# unimodule.net
KiCad netlist of a schematic drawn in EAGLE
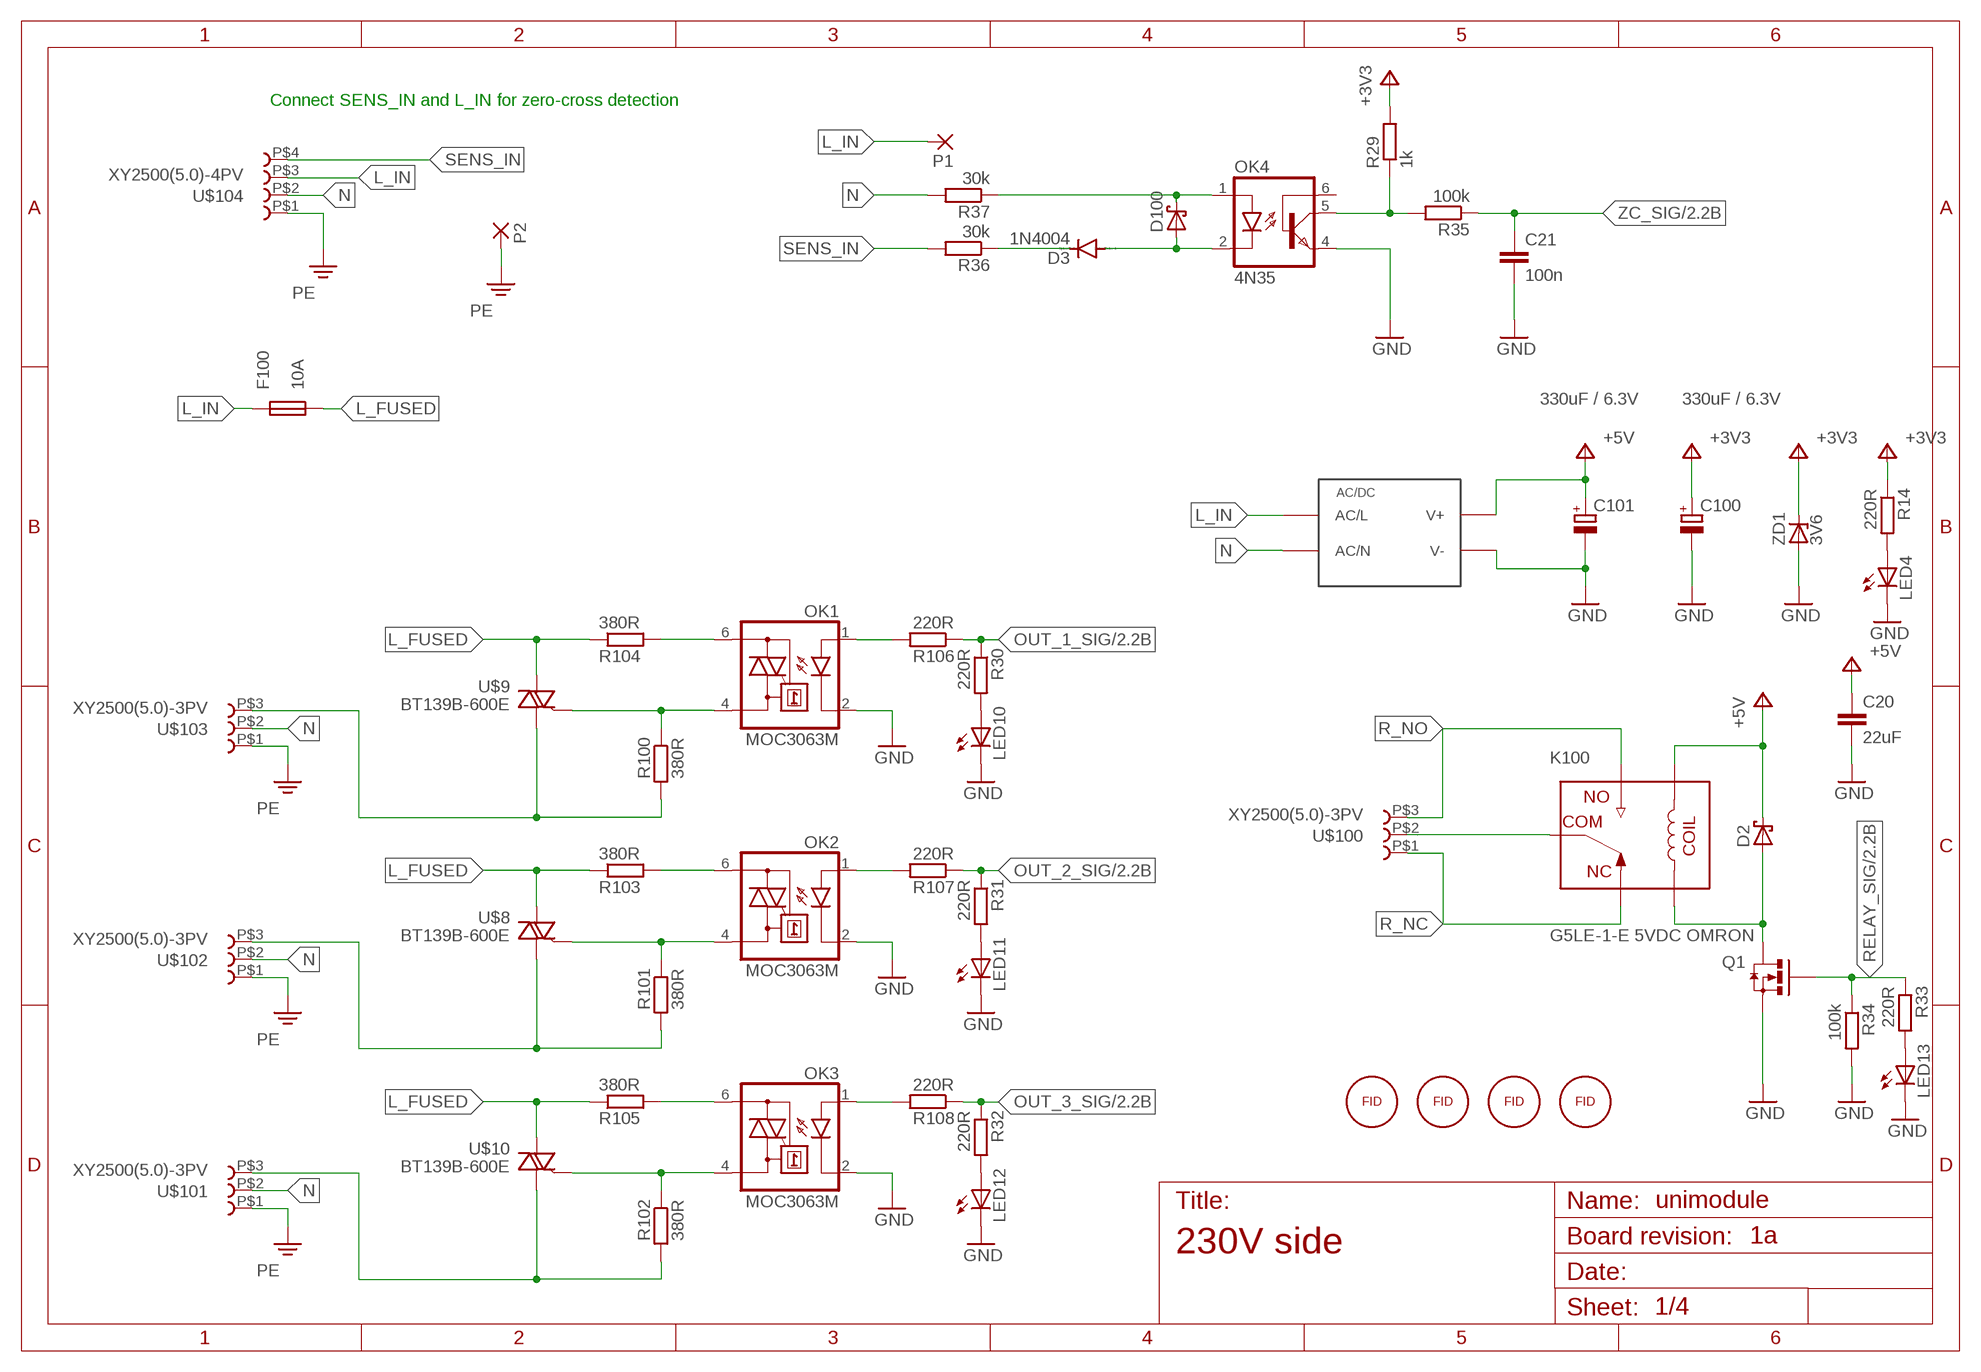
[diagram p0: schematic, sheet 1]
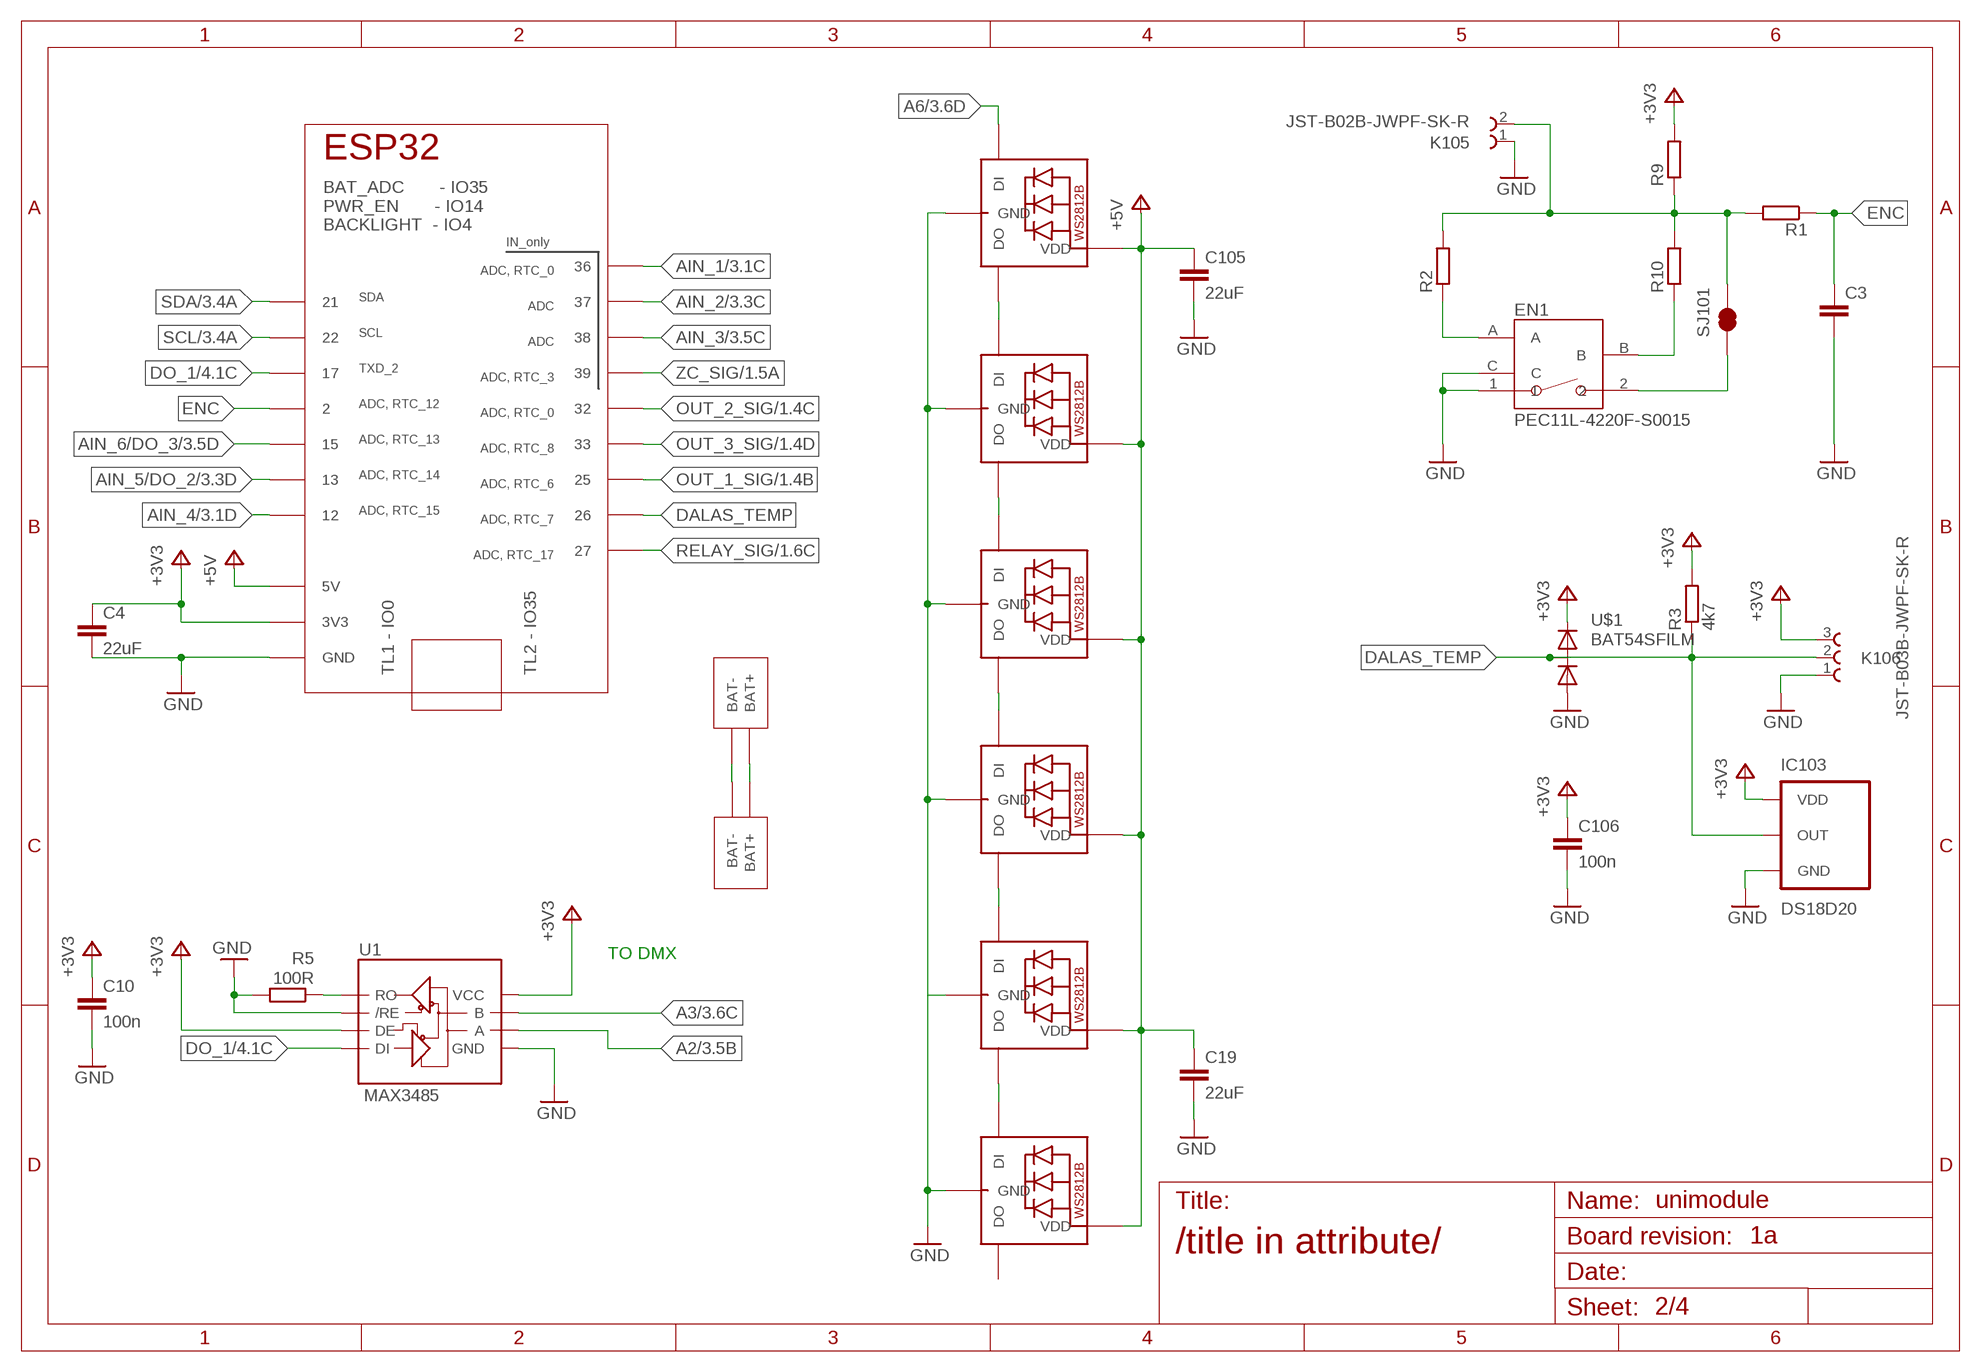
[diagram p1: schematic, sheet 2]
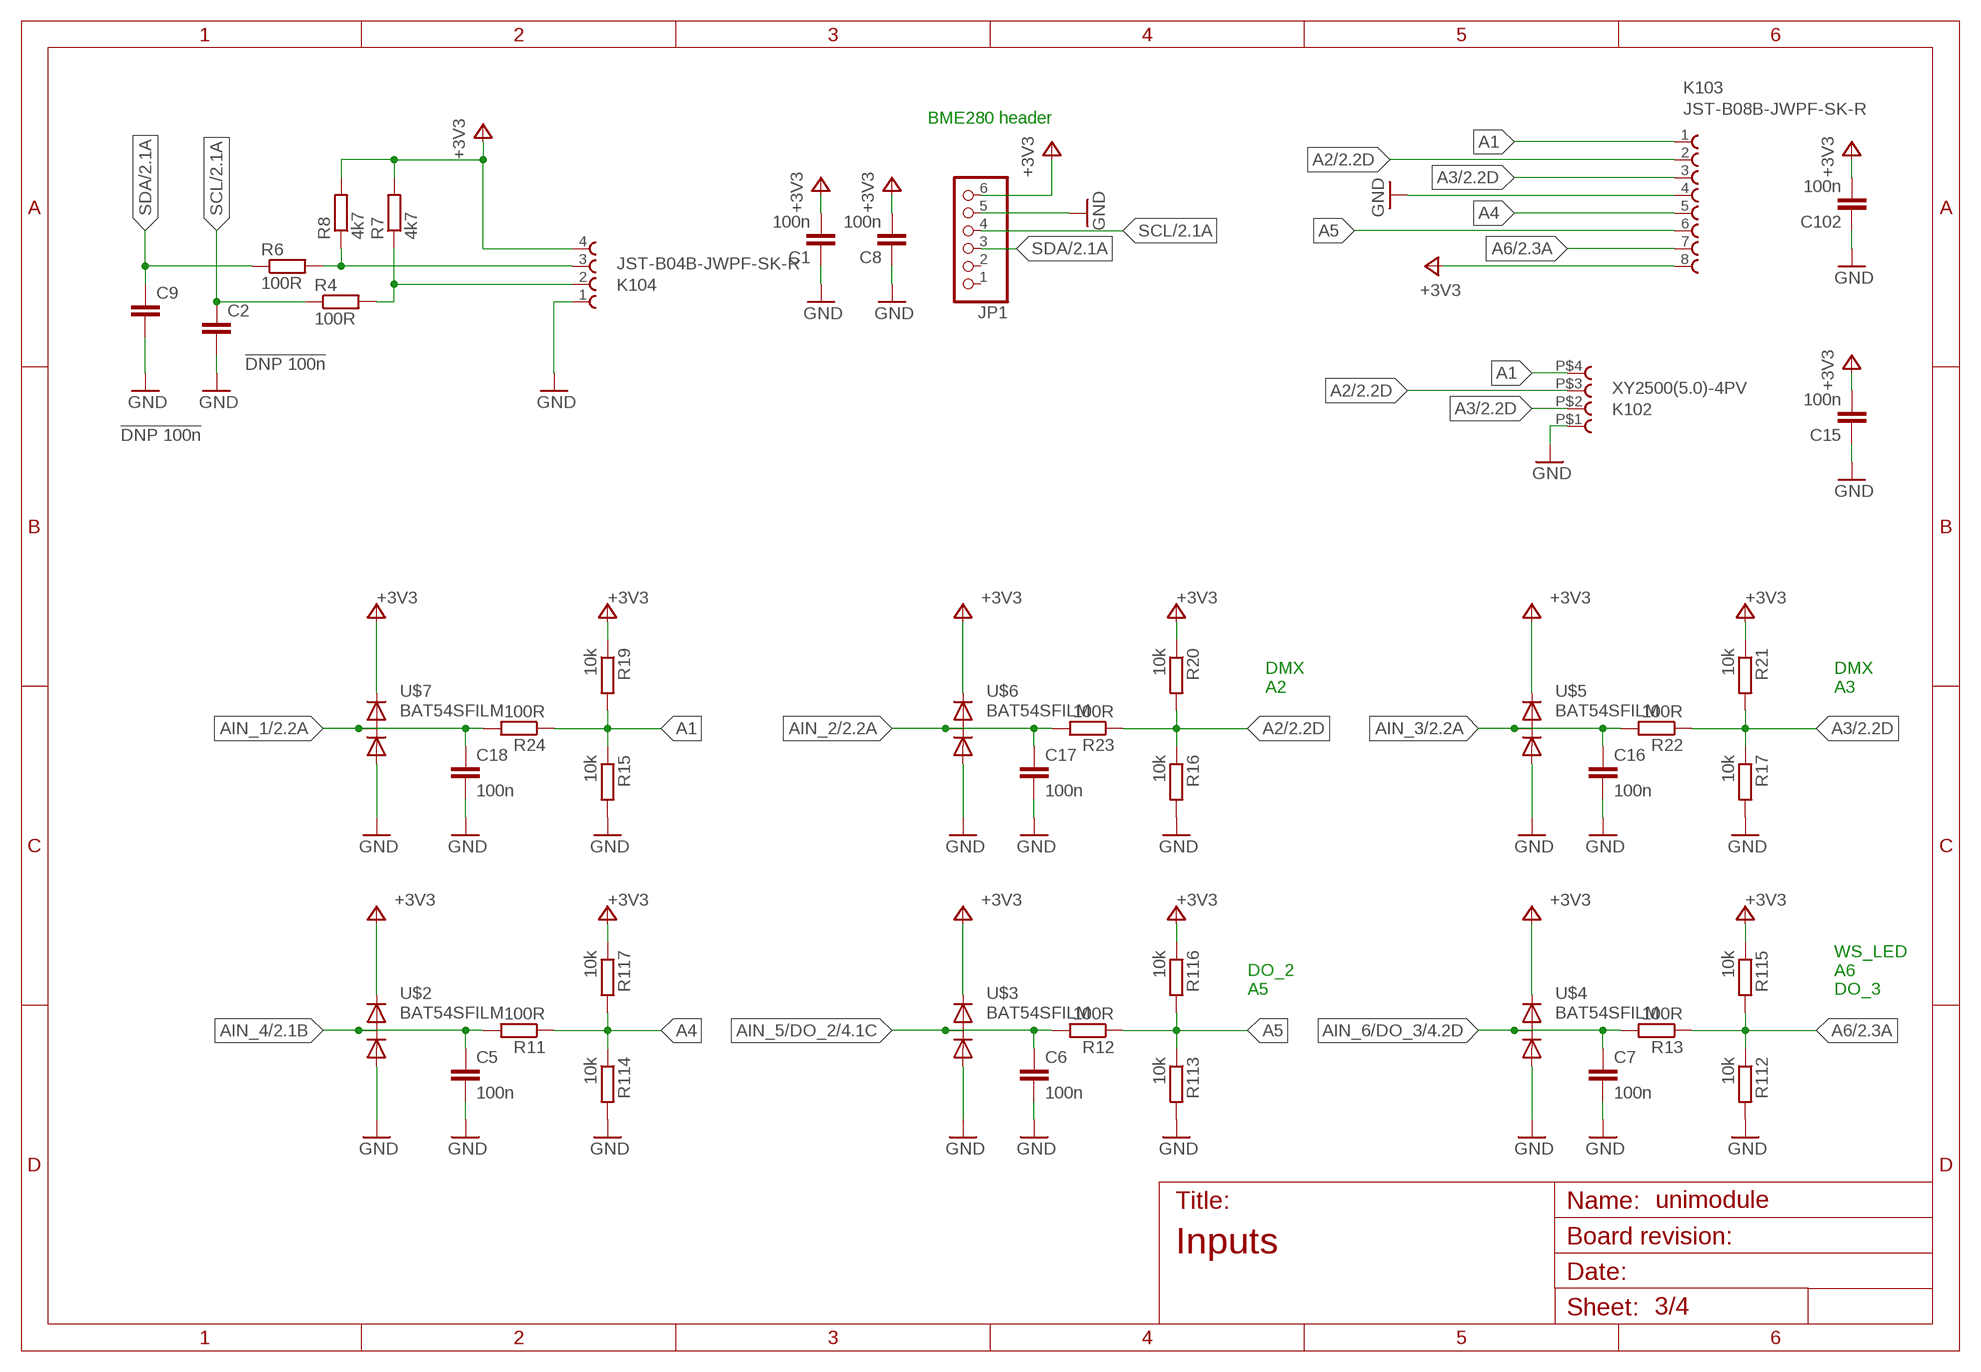
[diagram p2: schematic, sheet 3]
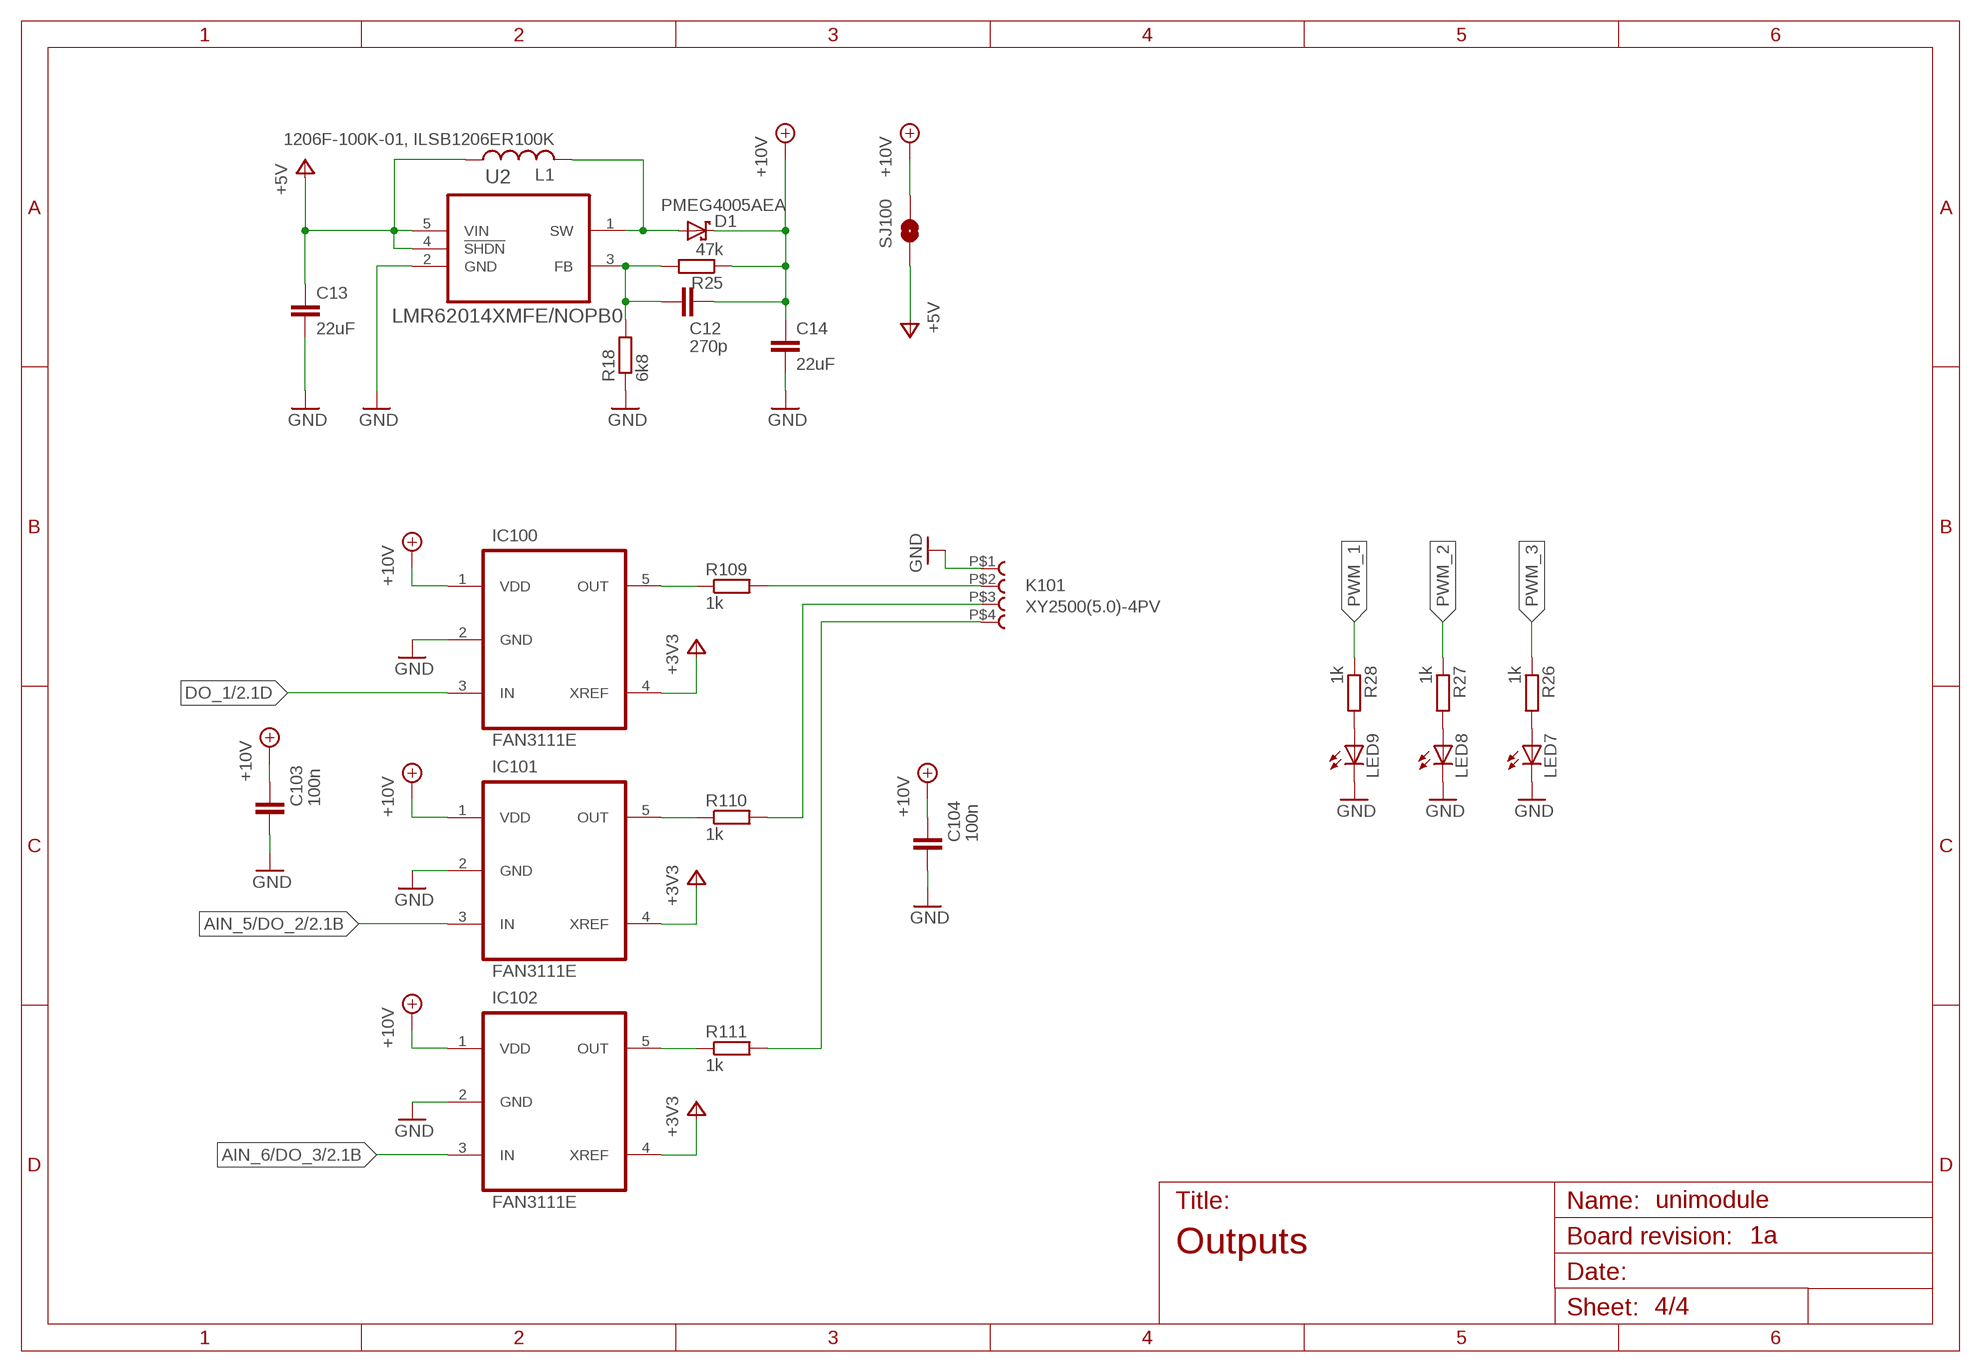
[diagram p3: schematic, sheet 4]

(export (version "E")
  (design (tool "Eeschema 10.0.6"))
  (components
    (comp (ref "C1")
      (value "100n")
      (footprint "eagle-import:C0603")
      (libsource (lib "eagle-import") (part "rcl_334_C-EUC0603"))
    )
    (comp (ref "C2")
      (value "!DNP 100n")
      (footprint "eagle-import:C0603")
      (libsource (lib "eagle-import") (part "rcl_334_C-EUC0603"))
    )
    (comp (ref "C5")
      (value "100n")
      (footprint "eagle-import:C0603")
      (libsource (lib "eagle-import") (part "rcl_334_C-EUC0603"))
    )
    (comp (ref "C6")
      (value "100n")
      (footprint "eagle-import:C0603")
      (libsource (lib "eagle-import") (part "rcl_334_C-EUC0603"))
    )
    (comp (ref "C7")
      (value "100n")
      (footprint "eagle-import:C0603")
      (libsource (lib "eagle-import") (part "rcl_334_C-EUC0603"))
    )
    (comp (ref "C8")
      (value "100n")
      (footprint "eagle-import:C0603")
      (libsource (lib "eagle-import") (part "rcl_334_C-EUC0603"))
    )
    (comp (ref "C9")
      (value "!DNP 100n")
      (footprint "eagle-import:C0603")
      (libsource (lib "eagle-import") (part "rcl_334_C-EUC0603"))
    )
    (comp (ref "C15")
      (value "100n")
      (footprint "eagle-import:C0603")
      (libsource (lib "eagle-import") (part "rcl_334_C-EUC0603"))
    )
    (comp (ref "C16")
      (value "100n")
      (footprint "eagle-import:C0603")
      (libsource (lib "eagle-import") (part "rcl_334_C-EUC0603"))
    )
    (comp (ref "C17")
      (value "100n")
      (footprint "eagle-import:C0603")
      (libsource (lib "eagle-import") (part "rcl_334_C-EUC0603"))
    )
    (comp (ref "C18")
      (value "100n")
      (footprint "eagle-import:C0603")
      (libsource (lib "eagle-import") (part "rcl_334_C-EUC0603"))
    )
    (comp (ref "C102")
      (value "100n")
      (footprint "eagle-import:C0603")
      (libsource (lib "eagle-import") (part "rcl_334_C-EUC0603"))
    )
    (comp (ref "JP1")
      (value "PINHD-1X6")
      (footprint "eagle-import:1X06")
      (libsource (lib "eagle-import") (part "PINHD-1X6"))
    )
    (comp (ref "K102")
      (value "XY2500(5.0)-4PV")
      (footprint "eagle-import:XY2500V-B_4P")
      (libsource (lib "eagle-import") (part "XY2500(5.0)-4PV"))
    )
    (comp (ref "K103")
      (value "JST-B08B-JWPF-SK-R")
      (footprint "eagle-import:JST-B08B-JWPF-SK-R")
      (libsource (lib "eagle-import") (part "JST-B08B-JWPF-SK-R"))
    )
    (comp (ref "K104")
      (value "JST-B04B-JWPF-SK-R")
      (footprint "eagle-import:JST-B04B-JWPF-SK-R")
      (libsource (lib "eagle-import") (part "JST-B04B-JWPF-SK-R"))
    )
    (comp (ref "R4")
      (value "100R")
      (footprint "eagle-import:R0603")
      (libsource (lib "eagle-import") (part "R-EU_R0603"))
    )
    (comp (ref "R6")
      (value "100R")
      (footprint "eagle-import:R0603")
      (libsource (lib "eagle-import") (part "R-EU_R0603"))
    )
    (comp (ref "R7")
      (value "4k7")
      (footprint "eagle-import:R0603")
      (libsource (lib "eagle-import") (part "R-EU_R0603"))
    )
    (comp (ref "R8")
      (value "4k7")
      (footprint "eagle-import:R0603")
      (libsource (lib "eagle-import") (part "R-EU_R0603"))
    )
    (comp (ref "R11")
      (value "100R")
      (footprint "eagle-import:R0603")
      (libsource (lib "eagle-import") (part "R-EU_R0603"))
    )
    (comp (ref "R12")
      (value "100R")
      (footprint "eagle-import:R0603")
      (libsource (lib "eagle-import") (part "R-EU_R0603"))
    )
    (comp (ref "R13")
      (value "100R")
      (footprint "eagle-import:R0603")
      (libsource (lib "eagle-import") (part "R-EU_R0603"))
    )
    (comp (ref "R15")
      (value "10k")
      (footprint "eagle-import:R0603")
      (libsource (lib "eagle-import") (part "R-EU_R0603"))
    )
    (comp (ref "R16")
      (value "10k")
      (footprint "eagle-import:R0603")
      (libsource (lib "eagle-import") (part "R-EU_R0603"))
    )
    (comp (ref "R17")
      (value "10k")
      (footprint "eagle-import:R0603")
      (libsource (lib "eagle-import") (part "R-EU_R0603"))
    )
    (comp (ref "R19")
      (value "10k")
      (footprint "eagle-import:R0603")
      (libsource (lib "eagle-import") (part "R-EU_R0603"))
    )
    (comp (ref "R20")
      (value "10k")
      (footprint "eagle-import:R0603")
      (libsource (lib "eagle-import") (part "R-EU_R0603"))
    )
    (comp (ref "R21")
      (value "10k")
      (footprint "eagle-import:R0603")
      (libsource (lib "eagle-import") (part "R-EU_R0603"))
    )
    (comp (ref "R22")
      (value "100R")
      (footprint "eagle-import:R0603")
      (libsource (lib "eagle-import") (part "R-EU_R0603"))
    )
    (comp (ref "R23")
      (value "100R")
      (footprint "eagle-import:R0603")
      (libsource (lib "eagle-import") (part "R-EU_R0603"))
    )
    (comp (ref "R24")
      (value "100R")
      (footprint "eagle-import:R0603")
      (libsource (lib "eagle-import") (part "R-EU_R0603"))
    )
    (comp (ref "R112")
      (value "10k")
      (footprint "eagle-import:R0603")
      (libsource (lib "eagle-import") (part "R-EU_R0603"))
    )
    (comp (ref "R113")
      (value "10k")
      (footprint "eagle-import:R0603")
      (libsource (lib "eagle-import") (part "R-EU_R0603"))
    )
    (comp (ref "R114")
      (value "10k")
      (footprint "eagle-import:R0603")
      (libsource (lib "eagle-import") (part "R-EU_R0603"))
    )
    (comp (ref "R115")
      (value "10k")
      (footprint "eagle-import:R0603")
      (libsource (lib "eagle-import") (part "R-EU_R0603"))
    )
    (comp (ref "R116")
      (value "10k")
      (footprint "eagle-import:R0603")
      (libsource (lib "eagle-import") (part "R-EU_R0603"))
    )
    (comp (ref "R117")
      (value "10k")
      (footprint "eagle-import:R0603")
      (libsource (lib "eagle-import") (part "R-EU_R0603"))
    )
    (comp (ref "U$2")
      (value "BAT54SFILM")
      (footprint "eagle-import:PG-SOT23")
      (libsource (lib "eagle-import") (part "BAT54SFILM"))
    )
    (comp (ref "U$3")
      (value "BAT54SFILM")
      (footprint "eagle-import:PG-SOT23")
      (libsource (lib "eagle-import") (part "BAT54SFILM"))
    )
    (comp (ref "U$4")
      (value "BAT54SFILM")
      (footprint "eagle-import:PG-SOT23")
      (libsource (lib "eagle-import") (part "BAT54SFILM"))
    )
    (comp (ref "U$5")
      (value "BAT54SFILM")
      (footprint "eagle-import:PG-SOT23")
      (libsource (lib "eagle-import") (part "BAT54SFILM"))
    )
    (comp (ref "U$6")
      (value "BAT54SFILM")
      (footprint "eagle-import:PG-SOT23")
      (libsource (lib "eagle-import") (part "BAT54SFILM"))
    )
    (comp (ref "U$7")
      (value "BAT54SFILM")
      (footprint "eagle-import:PG-SOT23")
      (libsource (lib "eagle-import") (part "BAT54SFILM"))
    )
    (comp (ref "C12")
      (value "270p")
      (footprint "eagle-import:C0603")
      (libsource (lib "eagle-import") (part "rcl_334_C-EUC0603"))
    )
    (comp (ref "C13")
      (value "22uF")
      (footprint "eagle-import:C1206")
      (libsource (lib "eagle-import") (part "rcl_334_C-EUC1206"))
    )
    (comp (ref "C14")
      (value "22uF")
      (footprint "eagle-import:C1206")
      (libsource (lib "eagle-import") (part "rcl_334_C-EUC1206"))
    )
    (comp (ref "C103")
      (value "100n")
      (footprint "eagle-import:C0603")
      (libsource (lib "eagle-import") (part "C-EUC0603"))
    )
    (comp (ref "C104")
      (value "100n")
      (footprint "eagle-import:C0603")
      (libsource (lib "eagle-import") (part "C-EUC0603"))
    )
    (comp (ref "D1")
      (value "PMEG4005AEA")
      (footprint "eagle-import:SOD123F")
      (libsource (lib "eagle-import") (part "PMEG4005EH"))
    )
    (comp (ref "IC100")
      (value "FAN3111E")
      (footprint "eagle-import:SOT23-5")
      (libsource (lib "eagle-import") (part "FAN3111E"))
    )
    (comp (ref "IC101")
      (value "FAN3111E")
      (footprint "eagle-import:SOT23-5")
      (libsource (lib "eagle-import") (part "FAN3111E"))
    )
    (comp (ref "IC102")
      (value "FAN3111E")
      (footprint "eagle-import:SOT23-5")
      (libsource (lib "eagle-import") (part "FAN3111E"))
    )
    (comp (ref "K101")
      (value "XY2500(5.0)-4PV")
      (footprint "eagle-import:XY2500V-B_4P")
      (libsource (lib "eagle-import") (part "XY2500(5.0)-4PV"))
    )
    (comp (ref "L1")
      (value "1206F-100K-01, ILSB1206ER100K")
      (footprint "eagle-import:C3216")
      (libsource (lib "eagle-import") (part "L-US"))
    )
    (comp (ref "LED7")
      (value "LED0603")
      (footprint "eagle-import:LED-0603")
      (libsource (lib "eagle-import") (part "LED0603"))
    )
    (comp (ref "LED8")
      (value "LED0603")
      (footprint "eagle-import:LED-0603")
      (libsource (lib "eagle-import") (part "LED0603"))
    )
    (comp (ref "LED9")
      (value "LED0603")
      (footprint "eagle-import:LED-0603")
      (libsource (lib "eagle-import") (part "LED0603"))
    )
    (comp (ref "R18")
      (value "6k8")
      (footprint "eagle-import:R0603")
      (libsource (lib "eagle-import") (part "R-EU_R0603"))
    )
    (comp (ref "R25")
      (value "47k")
      (footprint "eagle-import:R0603")
      (libsource (lib "eagle-import") (part "R-EU_R0603"))
    )
    (comp (ref "R26")
      (value "1k")
      (footprint "eagle-import:R0603")
      (libsource (lib "eagle-import") (part "R-EU_R0603"))
    )
    (comp (ref "R27")
      (value "1k")
      (footprint "eagle-import:R0603")
      (libsource (lib "eagle-import") (part "R-EU_R0603"))
    )
    (comp (ref "R28")
      (value "1k")
      (footprint "eagle-import:R0603")
      (libsource (lib "eagle-import") (part "R-EU_R0603"))
    )
    (comp (ref "R109")
      (value "1k")
      (footprint "eagle-import:R1206")
      (libsource (lib "eagle-import") (part "R-EU_R1206"))
    )
    (comp (ref "R110")
      (value "1k")
      (footprint "eagle-import:R1206")
      (libsource (lib "eagle-import") (part "R-EU_R1206"))
    )
    (comp (ref "R111")
      (value "1k")
      (footprint "eagle-import:R1206")
      (libsource (lib "eagle-import") (part "R-EU_R1206"))
    )
    (comp (ref "SJ100")
      (value "SMD-JUMPER")
      (footprint "eagle-import:SMD-JUMPER")
      (libsource (lib "eagle-import") (part "SMD-JUMPER"))
    )
    (comp (ref "U2")
      (value "LMR62014XMFE/NOPB0")
      (footprint "eagle-import:SOT23-5")
      (libsource (lib "eagle-import") (part "LMR62014XMFE/NOPB0"))
    )
    (comp (ref "C3")
      (value "C-EUC0603")
      (footprint "eagle-import:C0603")
      (libsource (lib "eagle-import") (part "rcl_334_C-EUC0603"))
    )
    (comp (ref "C4")
      (value "22uF")
      (footprint "eagle-import:C1206")
      (libsource (lib "eagle-import") (part "rcl_334_C-EUC1206"))
    )
    (comp (ref "C10")
      (value "100n")
      (footprint "eagle-import:C0603")
      (libsource (lib "eagle-import") (part "rcl_334_C-EUC0603"))
    )
    (comp (ref "C11")
      (value "DISP_BATSMD")
      (footprint "eagle-import:BAT_SMD")
      (libsource (lib "eagle-import") (part "DISP_BATSMD"))
    )
    (comp (ref "C19")
      (value "22uF")
      (footprint "eagle-import:C1206")
      (libsource (lib "eagle-import") (part "rcl_334_C-EUC1206"))
    )
    (comp (ref "C105")
      (value "22uF")
      (footprint "eagle-import:C1206")
      (libsource (lib "eagle-import") (part "rcl_334_C-EUC1206"))
    )
    (comp (ref "C106")
      (value "100n")
      (footprint "eagle-import:C0603")
      (libsource (lib "eagle-import") (part "rcl_334_C-EUC0603"))
    )
    (comp (ref "C107")
      (value "DISP_BAT2,54")
      (footprint "eagle-import:BAT_THT_254")
      (libsource (lib "eagle-import") (part "DISP_BAT2,54"))
    )
    (comp (ref "EN1")
      (value "PEC11L-4220F-S0015")
      (footprint "eagle-import:PEC11L-4220F-S0015")
      (fields
        (field (name "DIGIKEY_PARTNO") "PEC11L-4220F-S0015-ND")
        (field (name "MANUFACTURER") "Bourns Inc.")
        (field (name "CREATED_BY") "PCBLayout.com")
      )
      (libsource (lib "eagle-import") (part "PEC11L-4220F-S0015"))
    )
    (comp (ref "IC1")
      (value "TTGO_DISP")
      (footprint "eagle-import:TTGO_DISP_DEFAULT")
      (libsource (lib "eagle-import") (part "TTGO_DISP"))
    )
    (comp (ref "IC103")
      (value "DS18D20")
      (footprint "eagle-import:TO92")
      (libsource (lib "eagle-import") (part "DS18D20"))
    )
    (comp (ref "K105")
      (value "JST-B02B-JWPF-SK-R")
      (footprint "eagle-import:JST-B02B-JWPF-SK-R")
      (libsource (lib "eagle-import") (part "JST-B02B-JWPF-SK-R"))
    )
    (comp (ref "K106")
      (value "JST-B03B-JWPF-SK-R")
      (footprint "eagle-import:JST-B03B-JWPF-SK-R")
      (libsource (lib "eagle-import") (part "JST-B03B-JWPF-SK-R"))
    )
    (comp (ref "LED1")
      (value "WS2812B5050")
      (footprint "eagle-import:WS2812B")
      (libsource (lib "eagle-import") (part "WS2812B5050"))
    )
    (comp (ref "LED2")
      (value "WS2812B5050")
      (footprint "eagle-import:WS2812B")
      (libsource (lib "eagle-import") (part "WS2812B5050"))
    )
    (comp (ref "LED3")
      (value "WS2812B5050")
      (footprint "eagle-import:WS2812B")
      (libsource (lib "eagle-import") (part "WS2812B5050"))
    )
    (comp (ref "LED5")
      (value "WS2812B5050")
      (footprint "eagle-import:WS2812B")
      (libsource (lib "eagle-import") (part "WS2812B5050"))
    )
    (comp (ref "LED6")
      (value "WS2812B5050")
      (footprint "eagle-import:WS2812B")
      (libsource (lib "eagle-import") (part "WS2812B5050"))
    )
    (comp (ref "LED14")
      (value "WS2812B5050")
      (footprint "eagle-import:WS2812B")
      (libsource (lib "eagle-import") (part "WS2812B5050"))
    )
    (comp (ref "R1")
      (value "R-EU_R0603")
      (footprint "eagle-import:R0603")
      (libsource (lib "eagle-import") (part "R-EU_R0603"))
    )
    (comp (ref "R2")
      (value "R-EU_R0603")
      (footprint "eagle-import:R0603")
      (libsource (lib "eagle-import") (part "R-EU_R0603"))
    )
    (comp (ref "R3")
      (value "4k7")
      (footprint "eagle-import:R0603")
      (libsource (lib "eagle-import") (part "R-EU_R0603"))
    )
    (comp (ref "R5")
      (value "100R")
      (footprint "eagle-import:R0603")
      (libsource (lib "eagle-import") (part "R-EU_R0603"))
    )
    (comp (ref "R9")
      (value "R-EU_R0603")
      (footprint "eagle-import:R0603")
      (libsource (lib "eagle-import") (part "R-EU_R0603"))
    )
    (comp (ref "R10")
      (value "R-EU_R0603")
      (footprint "eagle-import:R0603")
      (libsource (lib "eagle-import") (part "R-EU_R0603"))
    )
    (comp (ref "SJ101")
      (value "NET-TIE")
      (footprint "eagle-import:SMD-JUMPER-TIE")
      (libsource (lib "eagle-import") (part "NET-TIE"))
    )
    (comp (ref "U$1")
      (value "BAT54SFILM")
      (footprint "eagle-import:PG-SOT23")
      (libsource (lib "eagle-import") (part "BAT54SFILM"))
    )
    (comp (ref "U1")
      (value "MAX3485")
      (footprint "eagle-import:SO08")
      (libsource (lib "eagle-import") (part "RS485SOIC"))
    )
    (comp (ref "C20")
      (value "22uF")
      (footprint "eagle-import:C1206")
      (libsource (lib "eagle-import") (part "rcl_334_C-EUC1206"))
    )
    (comp (ref "C21")
      (value "100n")
      (footprint "eagle-import:C0603")
      (libsource (lib "eagle-import") (part "rcl_334_C-EUC0603"))
    )
    (comp (ref "C100")
      (value "330uF / 6.3V")
      (footprint "eagle-import:E2,5-7")
      (libsource (lib "eagle-import") (part "CPOL-EUE2.5-7"))
    )
    (comp (ref "C101")
      (value "330uF / 6.3V")
      (footprint "eagle-import:E2,5-6")
      (libsource (lib "eagle-import") (part "CPOL-EUE2.5-6"))
    )
    (comp (ref "D2")
      (value "PMEG4005EH")
      (footprint "eagle-import:SOD123F")
      (libsource (lib "eagle-import") (part "PMEG4005EH"))
    )
    (comp (ref "D3")
      (value "1N4004")
      (footprint "eagle-import:DO41-10")
      (libsource (lib "eagle-import") (part "1N4004"))
    )
    (comp (ref "D100")
      (value "BAT46")
      (footprint "eagle-import:SOD123F")
      (libsource (lib "eagle-import") (part "BAT46"))
    )
    (comp (ref "F100")
      (value "10A")
      (footprint "eagle-import:SCHURTER_0751.0056_5X20")
      (libsource (lib "eagle-import") (part "FUSE20X5"))
    )
    (comp (ref "FD1")
      (value "FIDUCIAL-MARKER2MM")
      (footprint "eagle-import:1-2MM-FIDUCIAL")
      (libsource (lib "eagle-import") (part "FIDUCIAL-MARKER2MM"))
    )
    (comp (ref "FD2")
      (value "FIDUCIAL-MARKER2MM")
      (footprint "eagle-import:1-2MM-FIDUCIAL")
      (libsource (lib "eagle-import") (part "FIDUCIAL-MARKER2MM"))
    )
    (comp (ref "FD100")
      (value "FIDUCIAL-MARKER2MM")
      (footprint "eagle-import:1-2MM-FIDUCIAL")
      (libsource (lib "eagle-import") (part "FIDUCIAL-MARKER2MM"))
    )
    (comp (ref "FD101")
      (value "FIDUCIAL-MARKER2MM")
      (footprint "eagle-import:1-2MM-FIDUCIAL")
      (libsource (lib "eagle-import") (part "FIDUCIAL-MARKER2MM"))
    )
    (comp (ref "K100")
      (value "G5LE-1-E 5VDC OMRON")
      (footprint "eagle-import:JSM1-12V-5")
      (fields
        (field (name "DIGIKEY_PARTNO") "255-1240-ND")
        (field (name "MANUFACTURER") "Panasonic Electric Works")
        (field (name "MPN") "JSM1-12V-5")
        (field (name "CREATED_BY") "PCBLayout.com")
      )
      (libsource (lib "eagle-import") (part "JSM1-12V-5"))
    )
    (comp (ref "LED4")
      (value "LED0603")
      (footprint "eagle-import:LED-0603")
      (libsource (lib "eagle-import") (part "LED0603"))
    )
    (comp (ref "LED10")
      (value "LED0603")
      (footprint "eagle-import:LED-0603")
      (libsource (lib "eagle-import") (part "LED0603"))
    )
    (comp (ref "LED11")
      (value "LED0603")
      (footprint "eagle-import:LED-0603")
      (libsource (lib "eagle-import") (part "LED0603"))
    )
    (comp (ref "LED12")
      (value "LED0603")
      (footprint "eagle-import:LED-0603")
      (libsource (lib "eagle-import") (part "LED0603"))
    )
    (comp (ref "LED13")
      (value "LED0603")
      (footprint "eagle-import:LED-0603")
      (libsource (lib "eagle-import") (part "LED0603"))
    )
    (comp (ref "OK1")
      (value "MOC3063M")
      (footprint "eagle-import:DIL06")
      (libsource (lib "eagle-import") (part "MOC30"))
    )
    (comp (ref "OK2")
      (value "MOC3063M")
      (footprint "eagle-import:DIL06")
      (libsource (lib "eagle-import") (part "MOC30"))
    )
    (comp (ref "OK3")
      (value "MOC3063M")
      (footprint "eagle-import:DIL06")
      (libsource (lib "eagle-import") (part "MOC30"))
    )
    (comp (ref "OK4")
      (value "4N35")
      (footprint "eagle-import:DIL06")
      (fields (field (name "MF") "FAIRCHILD SEMICONDUCTOR"))
      (libsource (lib "eagle-import") (part "4N35"))
    )
    (comp (ref "P1")
      (value "WIRE-PAD1MM")
      (footprint "eagle-import:THT-PAD_0.5MM")
      (libsource (lib "eagle-import") (part "WIRE-PAD1MM"))
    )
    (comp (ref "P2")
      (value "WIRE-PAD3MM")
      (footprint "eagle-import:6MM2")
      (libsource (lib "eagle-import") (part "WIRE-PAD3MM"))
    )
    (comp (ref "Q1")
      (value "2N7002")
      (footprint "eagle-import:PG-SOT23")
      (libsource (lib "eagle-import") (part "2N7002"))
    )
    (comp (ref "R14")
      (value "220R")
      (footprint "eagle-import:R0603")
      (libsource (lib "eagle-import") (part "R-EU_R0603"))
    )
    (comp (ref "R29")
      (value "1k")
      (footprint "eagle-import:R0603")
      (libsource (lib "eagle-import") (part "R-EU_R0603"))
    )
    (comp (ref "R30")
      (value "220R")
      (footprint "eagle-import:R0603")
      (libsource (lib "eagle-import") (part "R-EU_R0603"))
    )
    (comp (ref "R31")
      (value "220R")
      (footprint "eagle-import:R0603")
      (libsource (lib "eagle-import") (part "R-EU_R0603"))
    )
    (comp (ref "R32")
      (value "220R")
      (footprint "eagle-import:R0603")
      (libsource (lib "eagle-import") (part "R-EU_R0603"))
    )
    (comp (ref "R33")
      (value "220R")
      (footprint "eagle-import:R0603")
      (libsource (lib "eagle-import") (part "R-EU_R0603"))
    )
    (comp (ref "R34")
      (value "100k")
      (footprint "eagle-import:R0603")
      (libsource (lib "eagle-import") (part "R-EU_R0603"))
    )
    (comp (ref "R35")
      (value "100k")
      (footprint "eagle-import:R0603")
      (libsource (lib "eagle-import") (part "R-EU_R0603"))
    )
    (comp (ref "R36")
      (value "30k")
      (footprint "eagle-import:0207_10")
      (libsource (lib "eagle-import") (part "R-EU_0207/10"))
    )
    (comp (ref "R37")
      (value "30k")
      (footprint "eagle-import:0207_10")
      (libsource (lib "eagle-import") (part "R-EU_0207/10"))
    )
    (comp (ref "R100")
      (value "380R")
      (footprint "eagle-import:R1206")
      (libsource (lib "eagle-import") (part "R-EU_R1206"))
    )
    (comp (ref "R101")
      (value "380R")
      (footprint "eagle-import:R1206")
      (libsource (lib "eagle-import") (part "R-EU_R1206"))
    )
    (comp (ref "R102")
      (value "380R")
      (footprint "eagle-import:R1206")
      (libsource (lib "eagle-import") (part "R-EU_R1206"))
    )
    (comp (ref "R103")
      (value "380R")
      (footprint "eagle-import:R1206")
      (libsource (lib "eagle-import") (part "R-EU_R1206"))
    )
    (comp (ref "R104")
      (value "380R")
      (footprint "eagle-import:R1206")
      (libsource (lib "eagle-import") (part "R-EU_R1206"))
    )
    (comp (ref "R105")
      (value "380R")
      (footprint "eagle-import:R1206")
      (libsource (lib "eagle-import") (part "R-EU_R1206"))
    )
    (comp (ref "R106")
      (value "220R")
      (footprint "eagle-import:R0603")
      (libsource (lib "eagle-import") (part "R-EU_R0603"))
    )
    (comp (ref "R107")
      (value "220R")
      (footprint "eagle-import:R0603")
      (libsource (lib "eagle-import") (part "R-EU_R0603"))
    )
    (comp (ref "R108")
      (value "220R")
      (footprint "eagle-import:R0603")
      (libsource (lib "eagle-import") (part "R-EU_R0603"))
    )
    (comp (ref "U$8")
      (value "BT139B-600E")
      (footprint "eagle-import:D2PACK")
      (libsource (lib "eagle-import") (part "BT139B"))
    )
    (comp (ref "U$9")
      (value "BT139B-600E")
      (footprint "eagle-import:D2PACK")
      (libsource (lib "eagle-import") (part "BT139B"))
    )
    (comp (ref "U$10")
      (value "BT139B-600E")
      (footprint "eagle-import:D2PACK")
      (libsource (lib "eagle-import") (part "BT139B"))
    )
    (comp (ref "U$100")
      (value "XY2500(5.0)-3PV")
      (footprint "eagle-import:XY2500V-B_3P")
      (libsource (lib "eagle-import") (part "XY2500(5.0)-3PV"))
    )
    (comp (ref "U$101")
      (value "XY2500(5.0)-3PV")
      (footprint "eagle-import:XY2500V-B_3P")
      (libsource (lib "eagle-import") (part "XY2500(5.0)-3PV"))
    )
    (comp (ref "U$102")
      (value "XY2500(5.0)-3PV")
      (footprint "eagle-import:XY2500V-B_3P")
      (libsource (lib "eagle-import") (part "XY2500(5.0)-3PV"))
    )
    (comp (ref "U$103")
      (value "XY2500(5.0)-3PV")
      (footprint "eagle-import:XY2500V-B_3P")
      (libsource (lib "eagle-import") (part "XY2500(5.0)-3PV"))
    )
    (comp (ref "U$104")
      (value "XY2500(5.0)-4PV")
      (footprint "eagle-import:XY2500V-B_4P")
      (libsource (lib "eagle-import") (part "XY2500(5.0)-4PV"))
    )
    (comp (ref "U$105")
      (value "IRM-03-05")
      (footprint "eagle-import:IRM-03")
      (libsource (lib "eagle-import") (part "IRM-03"))
    )
    (comp (ref "ZD1")
      (value "3V6")
      (footprint "eagle-import:SOD323-W")
      (libsource (lib "eagle-import") (part "BZD27SOD323-W"))
    )
  )
  (nets
    (net (code "1") (name "+3V3") (class "Default")
      (node (ref "C1") (pin "2") (pinfunction "2_2") (pintype "passive"))
      (node (ref "C10") (pin "1") (pinfunction "1_1") (pintype "passive"))
      (node (ref "C100") (pin "+") (pinfunction "+_+") (pintype "passive"))
      (node (ref "C102") (pin "2") (pinfunction "2_2") (pintype "passive"))
      (node (ref "C106") (pin "1") (pinfunction "1_1") (pintype "passive"))
      (node (ref "C15") (pin "2") (pinfunction "2_2") (pintype "passive"))
      (node (ref "C4") (pin "1") (pinfunction "1_1") (pintype "passive"))
      (node (ref "C8") (pin "2") (pinfunction "2_2") (pintype "passive"))
      (node (ref "IC1") (pin "3V3_1") (pinfunction "3V3_3V3_1") (pintype "bidirectional"))
      (node (ref "IC1") (pin "3V3_2") (pinfunction "3V3_3V3_2") (pintype "bidirectional"))
      (node (ref "IC100") (pin "4") (pinfunction "XREF_4") (pintype "output"))
      (node (ref "IC101") (pin "4") (pinfunction "XREF_4") (pintype "output"))
      (node (ref "IC102") (pin "4") (pinfunction "XREF_4") (pintype "output"))
      (node (ref "IC103") (pin "3") (pinfunction "VDD_3") (pintype "power_in"))
      (node (ref "JP1") (pin "6") (pinfunction "6_6") (pintype "passive"))
      (node (ref "K103") (pin "8") (pinfunction "8_8") (pintype "passive"))
      (node (ref "K104") (pin "4") (pinfunction "4_4") (pintype "passive"))
      (node (ref "K106") (pin "3") (pinfunction "3_3") (pintype "passive"))
      (node (ref "R115") (pin "1") (pinfunction "1_1") (pintype "passive"))
      (node (ref "R116") (pin "1") (pinfunction "1_1") (pintype "passive"))
      (node (ref "R117") (pin "1") (pinfunction "1_1") (pintype "passive"))
      (node (ref "R14") (pin "1") (pinfunction "1_1") (pintype "passive"))
      (node (ref "R19") (pin "1") (pinfunction "1_1") (pintype "passive"))
      (node (ref "R20") (pin "1") (pinfunction "1_1") (pintype "passive"))
      (node (ref "R21") (pin "1") (pinfunction "1_1") (pintype "passive"))
      (node (ref "R29") (pin "2") (pinfunction "2_2") (pintype "passive"))
      (node (ref "R3") (pin "2") (pinfunction "2_2") (pintype "passive"))
      (node (ref "R7") (pin "2") (pinfunction "2_2") (pintype "passive"))
      (node (ref "R8") (pin "2") (pinfunction "2_2") (pintype "passive"))
      (node (ref "R9") (pin "2") (pinfunction "2_2") (pintype "passive"))
      (node (ref "U$1") (pin "2") (pinfunction "C_2") (pintype "passive"))
      (node (ref "U$2") (pin "2") (pinfunction "C_2") (pintype "passive"))
      (node (ref "U$3") (pin "2") (pinfunction "C_2") (pintype "passive"))
      (node (ref "U$4") (pin "2") (pinfunction "C_2") (pintype "passive"))
      (node (ref "U$5") (pin "2") (pinfunction "C_2") (pintype "passive"))
      (node (ref "U$6") (pin "2") (pinfunction "C_2") (pintype "passive"))
      (node (ref "U$7") (pin "2") (pinfunction "C_2") (pintype "passive"))
      (node (ref "U1") (pin "3") (pinfunction "DE_3") (pintype "bidirectional"))
      (node (ref "U1") (pin "8") (pinfunction "VCC_8") (pintype "bidirectional"))
      (node (ref "ZD1") (pin "C") (pinfunction "C_C") (pintype "passive"))
    )
    (net (code "2") (name "+5V") (class "Default")
      (node (ref "C101") (pin "+") (pinfunction "+_+") (pintype "passive"))
      (node (ref "C105") (pin "1") (pinfunction "1_1") (pintype "passive"))
      (node (ref "C13") (pin "1") (pinfunction "1_1") (pintype "passive"))
      (node (ref "C19") (pin "1") (pinfunction "1_1") (pintype "passive"))
      (node (ref "C20") (pin "1") (pinfunction "1_1") (pintype "passive"))
      (node (ref "D2") (pin "C") (pinfunction "C_C") (pintype "passive"))
      (node (ref "IC1") (pin "5V") (pinfunction "5V_5V") (pintype "bidirectional"))
      (node (ref "K100") (pin "2") (pinfunction "2_2") (pintype "passive"))
      (node (ref "L1") (pin "1") (pinfunction "1_1") (pintype "passive"))
      (node (ref "LED1") (pin "1-VDD") (pinfunction "VDD_1-VDD") (pintype "power_in"))
      (node (ref "LED14") (pin "1-VDD") (pinfunction "VDD_1-VDD") (pintype "power_in"))
      (node (ref "LED2") (pin "1-VDD") (pinfunction "VDD_1-VDD") (pintype "power_in"))
      (node (ref "LED3") (pin "1-VDD") (pinfunction "VDD_1-VDD") (pintype "power_in"))
      (node (ref "LED5") (pin "1-VDD") (pinfunction "VDD_1-VDD") (pintype "power_in"))
      (node (ref "LED6") (pin "1-VDD") (pinfunction "VDD_1-VDD") (pintype "power_in"))
      (node (ref "SJ100") (pin "1") (pinfunction "1_1") (pintype "passive"))
      (node (ref "U$105") (pin "V+") (pinfunction "V+_V+") (pintype "bidirectional"))
      (node (ref "U2") (pin "4") (pinfunction "~{SHDN}_4") (pintype "input"))
      (node (ref "U2") (pin "5") (pinfunction "VIN_5") (pintype "power_in"))
    )
    (net (code "3") (name "+10V") (class "Default")
      (node (ref "C103") (pin "2") (pinfunction "2_2") (pintype "passive"))
      (node (ref "C104") (pin "2") (pinfunction "2_2") (pintype "passive"))
      (node (ref "C12") (pin "2") (pinfunction "2_2") (pintype "passive"))
      (node (ref "C14") (pin "1") (pinfunction "1_1") (pintype "passive"))
      (node (ref "D1") (pin "C") (pinfunction "C_C") (pintype "passive"))
      (node (ref "IC100") (pin "1") (pinfunction "VDD_1") (pintype "input"))
      (node (ref "IC101") (pin "1") (pinfunction "VDD_1") (pintype "input"))
      (node (ref "IC102") (pin "1") (pinfunction "VDD_1") (pintype "input"))
      (node (ref "R25") (pin "1") (pinfunction "1_1") (pintype "passive"))
      (node (ref "SJ100") (pin "2") (pinfunction "2_2") (pintype "passive"))
    )
    (net (code "4") (name "A1") (class "Default")
      (node (ref "K102") (pin "P$4") (pinfunction "4_P$4") (pintype "passive"))
      (node (ref "K103") (pin "1") (pinfunction "1_1") (pintype "passive"))
      (node (ref "R15") (pin "1") (pinfunction "1_1") (pintype "passive"))
      (node (ref "R19") (pin "2") (pinfunction "2_2") (pintype "passive"))
      (node (ref "R24") (pin "1") (pinfunction "1_1") (pintype "passive"))
    )
    (net (code "5") (name "A2") (class "Default")
      (node (ref "K102") (pin "P$3") (pinfunction "3_P$3") (pintype "passive"))
      (node (ref "K103") (pin "2") (pinfunction "2_2") (pintype "passive"))
      (node (ref "R16") (pin "1") (pinfunction "1_1") (pintype "passive"))
      (node (ref "R20") (pin "2") (pinfunction "2_2") (pintype "passive"))
      (node (ref "R23") (pin "1") (pinfunction "1_1") (pintype "passive"))
      (node (ref "U1") (pin "6") (pinfunction "A_6") (pintype "bidirectional"))
    )
    (net (code "6") (name "A3") (class "Default")
      (node (ref "K102") (pin "P$2") (pinfunction "2_P$2") (pintype "passive"))
      (node (ref "K103") (pin "3") (pinfunction "3_3") (pintype "passive"))
      (node (ref "R17") (pin "1") (pinfunction "1_1") (pintype "passive"))
      (node (ref "R21") (pin "2") (pinfunction "2_2") (pintype "passive"))
      (node (ref "R22") (pin "1") (pinfunction "1_1") (pintype "passive"))
      (node (ref "U1") (pin "7") (pinfunction "B_7") (pintype "bidirectional"))
    )
    (net (code "7") (name "A4") (class "Default")
      (node (ref "K103") (pin "5") (pinfunction "5_5") (pintype "passive"))
      (node (ref "R11") (pin "1") (pinfunction "1_1") (pintype "passive"))
      (node (ref "R114") (pin "1") (pinfunction "1_1") (pintype "passive"))
      (node (ref "R117") (pin "2") (pinfunction "2_2") (pintype "passive"))
    )
    (net (code "8") (name "A5") (class "Default")
      (node (ref "K103") (pin "6") (pinfunction "6_6") (pintype "passive"))
      (node (ref "R113") (pin "1") (pinfunction "1_1") (pintype "passive"))
      (node (ref "R116") (pin "2") (pinfunction "2_2") (pintype "passive"))
      (node (ref "R12") (pin "1") (pinfunction "1_1") (pintype "passive"))
    )
    (net (code "9") (name "A6") (class "Default")
      (node (ref "K103") (pin "7") (pinfunction "7_7") (pintype "passive"))
      (node (ref "LED1") (pin "4-DIN") (pinfunction "DI_4-DIN") (pintype "input"))
      (node (ref "R112") (pin "1") (pinfunction "1_1") (pintype "passive"))
      (node (ref "R115") (pin "2") (pinfunction "2_2") (pintype "passive"))
      (node (ref "R13") (pin "1") (pinfunction "1_1") (pintype "passive"))
    )
    (net (code "10") (name "AIN_1") (class "Default")
      (node (ref "C18") (pin "1") (pinfunction "1_1") (pintype "passive"))
      (node (ref "IC1") (pin "36") (pinfunction "36_36") (pintype "bidirectional"))
      (node (ref "R24") (pin "2") (pinfunction "2_2") (pintype "passive"))
      (node (ref "U$7") (pin "3") (pinfunction "COMMON_3") (pintype "passive"))
    )
    (net (code "11") (name "AIN_2") (class "Default")
      (node (ref "C17") (pin "1") (pinfunction "1_1") (pintype "passive"))
      (node (ref "IC1") (pin "37") (pinfunction "37_37") (pintype "bidirectional"))
      (node (ref "R23") (pin "2") (pinfunction "2_2") (pintype "passive"))
      (node (ref "U$6") (pin "3") (pinfunction "COMMON_3") (pintype "passive"))
    )
    (net (code "12") (name "AIN_3") (class "Default")
      (node (ref "C16") (pin "1") (pinfunction "1_1") (pintype "passive"))
      (node (ref "IC1") (pin "38") (pinfunction "38_38") (pintype "bidirectional"))
      (node (ref "R22") (pin "2") (pinfunction "2_2") (pintype "passive"))
      (node (ref "U$5") (pin "3") (pinfunction "COMMON_3") (pintype "passive"))
    )
    (net (code "13") (name "AIN_4") (class "Default")
      (node (ref "C5") (pin "1") (pinfunction "1_1") (pintype "passive"))
      (node (ref "IC1") (pin "12") (pinfunction "12_12") (pintype "bidirectional"))
      (node (ref "R11") (pin "2") (pinfunction "2_2") (pintype "passive"))
      (node (ref "U$2") (pin "3") (pinfunction "COMMON_3") (pintype "passive"))
    )
    (net (code "14") (name "AIN_5{slash}DO_2") (class "Default")
      (node (ref "C6") (pin "1") (pinfunction "1_1") (pintype "passive"))
      (node (ref "IC1") (pin "13") (pinfunction "13_13") (pintype "bidirectional"))
      (node (ref "IC101") (pin "3") (pinfunction "IN_3") (pintype "input"))
      (node (ref "R12") (pin "2") (pinfunction "2_2") (pintype "passive"))
      (node (ref "U$3") (pin "3") (pinfunction "COMMON_3") (pintype "passive"))
    )
    (net (code "15") (name "AIN_6{slash}DO_3") (class "Default")
      (node (ref "C7") (pin "1") (pinfunction "1_1") (pintype "passive"))
      (node (ref "IC1") (pin "15") (pinfunction "15_15") (pintype "bidirectional"))
      (node (ref "IC102") (pin "3") (pinfunction "IN_3") (pintype "input"))
      (node (ref "R13") (pin "2") (pinfunction "2_2") (pintype "passive"))
      (node (ref "U$4") (pin "3") (pinfunction "COMMON_3") (pintype "passive"))
    )
    (net (code "16") (name "DALAS_TEMP") (class "Default")
      (node (ref "IC1") (pin "26") (pinfunction "26_26") (pintype "bidirectional"))
      (node (ref "IC103") (pin "2") (pinfunction "OUT_2") (pintype "output"))
      (node (ref "K106") (pin "2") (pinfunction "2_2") (pintype "passive"))
      (node (ref "R3") (pin "1") (pinfunction "1_1") (pintype "passive"))
      (node (ref "U$1") (pin "3") (pinfunction "COMMON_3") (pintype "passive"))
    )
    (net (code "17") (name "DO_1") (class "Default")
      (node (ref "IC1") (pin "17") (pinfunction "17_17") (pintype "bidirectional"))
      (node (ref "IC100") (pin "3") (pinfunction "IN_3") (pintype "input"))
      (node (ref "U1") (pin "4") (pinfunction "DI_4") (pintype "bidirectional"))
    )
    (net (code "18") (name "ENC") (class "Default")
      (node (ref "C3") (pin "1") (pinfunction "1_1") (pintype "passive"))
      (node (ref "IC1") (pin "2") (pinfunction "2_2") (pintype "bidirectional"))
      (node (ref "R1") (pin "1") (pinfunction "1_1") (pintype "passive"))
    )
    (net (code "19") (name "GND") (class "Default")
      (node (ref "C1") (pin "1") (pinfunction "1_1") (pintype "passive"))
      (node (ref "C10") (pin "2") (pinfunction "2_2") (pintype "passive"))
      (node (ref "C100") (pin "-") (pinfunction "-_-") (pintype "passive"))
      (node (ref "C101") (pin "-") (pinfunction "-_-") (pintype "passive"))
      (node (ref "C102") (pin "1") (pinfunction "1_1") (pintype "passive"))
      (node (ref "C103") (pin "1") (pinfunction "1_1") (pintype "passive"))
      (node (ref "C104") (pin "1") (pinfunction "1_1") (pintype "passive"))
      (node (ref "C105") (pin "2") (pinfunction "2_2") (pintype "passive"))
      (node (ref "C106") (pin "2") (pinfunction "2_2") (pintype "passive"))
      (node (ref "C13") (pin "2") (pinfunction "2_2") (pintype "passive"))
      (node (ref "C14") (pin "2") (pinfunction "2_2") (pintype "passive"))
      (node (ref "C15") (pin "1") (pinfunction "1_1") (pintype "passive"))
      (node (ref "C16") (pin "2") (pinfunction "2_2") (pintype "passive"))
      (node (ref "C17") (pin "2") (pinfunction "2_2") (pintype "passive"))
      (node (ref "C18") (pin "2") (pinfunction "2_2") (pintype "passive"))
      (node (ref "C19") (pin "2") (pinfunction "2_2") (pintype "passive"))
      (node (ref "C2") (pin "2") (pinfunction "2_2") (pintype "passive"))
      (node (ref "C20") (pin "2") (pinfunction "2_2") (pintype "passive"))
      (node (ref "C21") (pin "2") (pinfunction "2_2") (pintype "passive"))
      (node (ref "C3") (pin "2") (pinfunction "2_2") (pintype "passive"))
      (node (ref "C4") (pin "2") (pinfunction "2_2") (pintype "passive"))
      (node (ref "C5") (pin "2") (pinfunction "2_2") (pintype "passive"))
      (node (ref "C6") (pin "2") (pinfunction "2_2") (pintype "passive"))
      (node (ref "C7") (pin "2") (pinfunction "2_2") (pintype "passive"))
      (node (ref "C8") (pin "1") (pinfunction "1_1") (pintype "passive"))
      (node (ref "C9") (pin "2") (pinfunction "2_2") (pintype "passive"))
      (node (ref "EN1") (pin "1") (pinfunction "1_1") (pintype "passive"))
      (node (ref "EN1") (pin "C") (pinfunction "C_C") (pintype "passive"))
      (node (ref "IC1") (pin "GND_1") (pinfunction "GND_GND_1") (pintype "bidirectional"))
      (node (ref "IC1") (pin "GND_2") (pinfunction "GND_GND_2") (pintype "bidirectional"))
      (node (ref "IC1") (pin "GND_3") (pinfunction "GND_GND_3") (pintype "bidirectional"))
      (node (ref "IC1") (pin "GND_4") (pinfunction "GND_GND_4") (pintype "bidirectional"))
      (node (ref "IC1") (pin "GND_5") (pinfunction "GND_GND_5") (pintype "bidirectional"))
      (node (ref "IC100") (pin "2") (pinfunction "GND_2") (pintype "power_in"))
      (node (ref "IC101") (pin "2") (pinfunction "GND_2") (pintype "power_in"))
      (node (ref "IC102") (pin "2") (pinfunction "GND_2") (pintype "power_in"))
      (node (ref "IC103") (pin "1") (pinfunction "GND_1") (pintype "power_in"))
      (node (ref "JP1") (pin "5") (pinfunction "5_5") (pintype "passive"))
      (node (ref "K101") (pin "P$1") (pinfunction "1_P$1") (pintype "passive"))
      (node (ref "K102") (pin "P$1") (pinfunction "1_P$1") (pintype "passive"))
      (node (ref "K103") (pin "4") (pinfunction "4_4") (pintype "passive"))
      (node (ref "K104") (pin "1") (pinfunction "1_1") (pintype "passive"))
      (node (ref "K105") (pin "1") (pinfunction "1_1") (pintype "passive"))
      (node (ref "K106") (pin "1") (pinfunction "1_1") (pintype "passive"))
      (node (ref "LED1") (pin "3-GND") (pinfunction "GND_3-GND") (pintype "power_in"))
      (node (ref "LED10") (pin "C") (pinfunction "C_C") (pintype "passive"))
      (node (ref "LED11") (pin "C") (pinfunction "C_C") (pintype "passive"))
      (node (ref "LED12") (pin "C") (pinfunction "C_C") (pintype "passive"))
      (node (ref "LED13") (pin "C") (pinfunction "C_C") (pintype "passive"))
      (node (ref "LED14") (pin "3-GND") (pinfunction "GND_3-GND") (pintype "power_in"))
      (node (ref "LED2") (pin "3-GND") (pinfunction "GND_3-GND") (pintype "power_in"))
      (node (ref "LED3") (pin "3-GND") (pinfunction "GND_3-GND") (pintype "power_in"))
      (node (ref "LED4") (pin "C") (pinfunction "C_C") (pintype "passive"))
      (node (ref "LED5") (pin "3-GND") (pinfunction "GND_3-GND") (pintype "power_in"))
      (node (ref "LED6") (pin "3-GND") (pinfunction "GND_3-GND") (pintype "power_in"))
      (node (ref "LED7") (pin "C") (pinfunction "C_C") (pintype "passive"))
      (node (ref "LED8") (pin "C") (pinfunction "C_C") (pintype "passive"))
      (node (ref "LED9") (pin "C") (pinfunction "C_C") (pintype "passive"))
      (node (ref "OK1") (pin "2") (pinfunction "C_2") (pintype "passive"))
      (node (ref "OK2") (pin "2") (pinfunction "C_2") (pintype "passive"))
      (node (ref "OK3") (pin "2") (pinfunction "C_2") (pintype "passive"))
      (node (ref "OK4") (pin "4") (pinfunction "EMI_4") (pintype "passive"))
      (node (ref "Q1") (pin "2") (pinfunction "S_2") (pintype "passive"))
      (node (ref "R112") (pin "2") (pinfunction "2_2") (pintype "passive"))
      (node (ref "R113") (pin "2") (pinfunction "2_2") (pintype "passive"))
      (node (ref "R114") (pin "2") (pinfunction "2_2") (pintype "passive"))
      (node (ref "R15") (pin "2") (pinfunction "2_2") (pintype "passive"))
      (node (ref "R16") (pin "2") (pinfunction "2_2") (pintype "passive"))
      (node (ref "R17") (pin "2") (pinfunction "2_2") (pintype "passive"))
      (node (ref "R18") (pin "1") (pinfunction "1_1") (pintype "passive"))
      (node (ref "R34") (pin "2") (pinfunction "2_2") (pintype "passive"))
      (node (ref "R5") (pin "2") (pinfunction "2_2") (pintype "passive"))
      (node (ref "U$1") (pin "1") (pinfunction "A_1") (pintype "passive"))
      (node (ref "U$105") (pin "V-") (pinfunction "V-_V-") (pintype "bidirectional"))
      (node (ref "U$2") (pin "1") (pinfunction "A_1") (pintype "passive"))
      (node (ref "U$3") (pin "1") (pinfunction "A_1") (pintype "passive"))
      (node (ref "U$4") (pin "1") (pinfunction "A_1") (pintype "passive"))
      (node (ref "U$5") (pin "1") (pinfunction "A_1") (pintype "passive"))
      (node (ref "U$6") (pin "1") (pinfunction "A_1") (pintype "passive"))
      (node (ref "U$7") (pin "1") (pinfunction "A_1") (pintype "passive"))
      (node (ref "U1") (pin "2") (pinfunction "/RE_2") (pintype "bidirectional"))
      (node (ref "U1") (pin "5") (pinfunction "GND_5") (pintype "bidirectional"))
      (node (ref "U2") (pin "2") (pinfunction "GND_2") (pintype "passive"))
      (node (ref "ZD1") (pin "A") (pinfunction "A_A") (pintype "passive"))
    )
    (net (code "20") (name "L_FUSED") (class "Default")
      (node (ref "F100") (pin "I_1") (pinfunction "1_I_1") (pintype "passive"))
      (node (ref "F100") (pin "I_2") (pinfunction "1_I_2") (pintype "passive"))
      (node (ref "F100") (pin "I_3") (pinfunction "1_I_3") (pintype "passive"))
      (node (ref "R103") (pin "1") (pinfunction "1_1") (pintype "passive"))
      (node (ref "R104") (pin "1") (pinfunction "1_1") (pintype "passive"))
      (node (ref "R105") (pin "1") (pinfunction "1_1") (pintype "passive"))
      (node (ref "U$10") (pin "2") (pinfunction "A2_2") (pintype "passive"))
      (node (ref "U$8") (pin "2") (pinfunction "A2_2") (pintype "passive"))
      (node (ref "U$9") (pin "2") (pinfunction "A2_2") (pintype "passive"))
    )
    (net (code "21") (name "L_IN") (class "Default")
      (node (ref "F100") (pin "O_1") (pinfunction "2_O_1") (pintype "passive"))
      (node (ref "F100") (pin "O_2") (pinfunction "2_O_2") (pintype "passive"))
      (node (ref "F100") (pin "O_3") (pinfunction "2_O_3") (pintype "passive"))
      (node (ref "P1") (pin "P$1") (pinfunction "P_P$1") (pintype "passive"))
      (node (ref "U$104") (pin "P$3") (pinfunction "3_P$3") (pintype "passive"))
      (node (ref "U$105") (pin "AC/L") (pinfunction "AC/L_AC/L") (pintype "bidirectional"))
    )
    (net (code "22") (name "N") (class "Default")
      (node (ref "R37") (pin "2") (pinfunction "2_2") (pintype "passive"))
      (node (ref "U$101") (pin "P$2") (pinfunction "2_P$2") (pintype "passive"))
      (node (ref "U$102") (pin "P$2") (pinfunction "2_P$2") (pintype "passive"))
      (node (ref "U$103") (pin "P$2") (pinfunction "2_P$2") (pintype "passive"))
      (node (ref "U$104") (pin "P$2") (pinfunction "2_P$2") (pintype "passive"))
      (node (ref "U$105") (pin "AC/N") (pinfunction "AC/N_AC/N") (pintype "bidirectional"))
    )
    (net (code "23") (name "Net-(C107-PadBAT+)") (class "Default")
      (node (ref "C107") (pin "BAT+") (pinfunction "BAT+_BAT+") (pintype "bidirectional"))
      (node (ref "C11") (pin "BAT+") (pinfunction "BAT+_BAT+") (pintype "bidirectional"))
    )
    (net (code "24") (name "Net-(C107-PadBAT-)") (class "Default")
      (node (ref "C107") (pin "BAT-") (pinfunction "BAT-_BAT-") (pintype "bidirectional"))
      (node (ref "C11") (pin "BAT-") (pinfunction "BAT-_BAT-") (pintype "bidirectional"))
    )
    (net (code "25") (name "Net-(D3-PadC)") (class "Default")
      (node (ref "D3") (pin "C") (pinfunction "C_C") (pintype "passive"))
      (node (ref "R36") (pin "1") (pinfunction "1_1") (pintype "passive"))
    )
    (net (code "26") (name "Net-(EN1-Pad2)") (class "Default")
      (node (ref "EN1") (pin "2") (pinfunction "2_2") (pintype "passive"))
      (node (ref "SJ101") (pin "1") (pinfunction "1_1") (pintype "passive"))
    )
    (net (code "27") (name "Net-(EN1-PadA)") (class "Default")
      (node (ref "EN1") (pin "A") (pinfunction "A_A") (pintype "passive"))
      (node (ref "R2") (pin "1") (pinfunction "1_1") (pintype "passive"))
    )
    (net (code "28") (name "Net-(EN1-PadB)") (class "Default")
      (node (ref "EN1") (pin "B") (pinfunction "B_B") (pintype "passive"))
      (node (ref "R10") (pin "1") (pinfunction "1_1") (pintype "passive"))
    )
    (net (code "29") (name "Net-(IC100-OUT)") (class "Default")
      (node (ref "IC100") (pin "5") (pinfunction "OUT_5") (pintype "power_in"))
      (node (ref "R109") (pin "1") (pinfunction "1_1") (pintype "passive"))
    )
    (net (code "30") (name "Net-(IC101-OUT)") (class "Default")
      (node (ref "IC101") (pin "5") (pinfunction "OUT_5") (pintype "power_in"))
      (node (ref "R110") (pin "1") (pinfunction "1_1") (pintype "passive"))
    )
    (net (code "31") (name "Net-(IC102-OUT)") (class "Default")
      (node (ref "IC102") (pin "5") (pinfunction "OUT_5") (pintype "power_in"))
      (node (ref "R111") (pin "1") (pinfunction "1_1") (pintype "passive"))
    )
    (net (code "32") (name "Net-(K104-Pad2)") (class "Default")
      (node (ref "K104") (pin "2") (pinfunction "2_2") (pintype "passive"))
      (node (ref "R4") (pin "2") (pinfunction "2_2") (pintype "passive"))
      (node (ref "R7") (pin "1") (pinfunction "1_1") (pintype "passive"))
    )
    (net (code "33") (name "Net-(K104-Pad3)") (class "Default")
      (node (ref "K104") (pin "3") (pinfunction "3_3") (pintype "passive"))
      (node (ref "R6") (pin "2") (pinfunction "2_2") (pintype "passive"))
      (node (ref "R8") (pin "1") (pinfunction "1_1") (pintype "passive"))
    )
    (net (code "34") (name "Net-(K105-Pad2)") (class "Default")
      (node (ref "K105") (pin "2") (pinfunction "2_2") (pintype "passive"))
      (node (ref "R1") (pin "2") (pinfunction "2_2") (pintype "passive"))
      (node (ref "R10") (pin "2") (pinfunction "2_2") (pintype "passive"))
      (node (ref "R2") (pin "2") (pinfunction "2_2") (pintype "passive"))
      (node (ref "R9") (pin "1") (pinfunction "1_1") (pintype "passive"))
      (node (ref "SJ101") (pin "2") (pinfunction "2_2") (pintype "passive"))
    )
    (net (code "35") (name "Net-(LED1-DO)") (class "Default")
      (node (ref "LED1") (pin "2-DOUT") (pinfunction "DO_2-DOUT") (pintype "output"))
      (node (ref "LED2") (pin "4-DIN") (pinfunction "DI_4-DIN") (pintype "input"))
    )
    (net (code "36") (name "Net-(LED2-DO)") (class "Default")
      (node (ref "LED2") (pin "2-DOUT") (pinfunction "DO_2-DOUT") (pintype "output"))
      (node (ref "LED3") (pin "4-DIN") (pinfunction "DI_4-DIN") (pintype "input"))
    )
    (net (code "37") (name "Net-(LED3-DO)") (class "Default")
      (node (ref "LED3") (pin "2-DOUT") (pinfunction "DO_2-DOUT") (pintype "output"))
      (node (ref "LED5") (pin "4-DIN") (pinfunction "DI_4-DIN") (pintype "input"))
    )
    (net (code "38") (name "Net-(LED4-PadA)") (class "Default")
      (node (ref "LED4") (pin "A") (pinfunction "A_A") (pintype "passive"))
      (node (ref "R14") (pin "2") (pinfunction "2_2") (pintype "passive"))
    )
    (net (code "39") (name "Net-(LED5-DO)") (class "Default")
      (node (ref "LED5") (pin "2-DOUT") (pinfunction "DO_2-DOUT") (pintype "output"))
      (node (ref "LED6") (pin "4-DIN") (pinfunction "DI_4-DIN") (pintype "input"))
    )
    (net (code "40") (name "Net-(LED7-PadA)") (class "Default")
      (node (ref "LED7") (pin "A") (pinfunction "A_A") (pintype "passive"))
      (node (ref "R26") (pin "2") (pinfunction "2_2") (pintype "passive"))
    )
    (net (code "41") (name "Net-(LED8-PadA)") (class "Default")
      (node (ref "LED8") (pin "A") (pinfunction "A_A") (pintype "passive"))
      (node (ref "R27") (pin "2") (pinfunction "2_2") (pintype "passive"))
    )
    (net (code "42") (name "Net-(LED9-PadA)") (class "Default")
      (node (ref "LED9") (pin "A") (pinfunction "A_A") (pintype "passive"))
      (node (ref "R28") (pin "2") (pinfunction "2_2") (pintype "passive"))
    )
    (net (code "43") (name "Net-(LED10-PadA)") (class "Default")
      (node (ref "LED10") (pin "A") (pinfunction "A_A") (pintype "passive"))
      (node (ref "R30") (pin "2") (pinfunction "2_2") (pintype "passive"))
    )
    (net (code "44") (name "Net-(LED11-PadA)") (class "Default")
      (node (ref "LED11") (pin "A") (pinfunction "A_A") (pintype "passive"))
      (node (ref "R31") (pin "2") (pinfunction "2_2") (pintype "passive"))
    )
    (net (code "45") (name "Net-(LED12-PadA)") (class "Default")
      (node (ref "LED12") (pin "A") (pinfunction "A_A") (pintype "passive"))
      (node (ref "R32") (pin "2") (pinfunction "2_2") (pintype "passive"))
    )
    (net (code "46") (name "Net-(LED13-PadA)") (class "Default")
      (node (ref "LED13") (pin "A") (pinfunction "A_A") (pintype "passive"))
      (node (ref "R33") (pin "2") (pinfunction "2_2") (pintype "passive"))
    )
    (net (code "47") (name "Net-(LED14-DI)") (class "Default")
      (node (ref "LED14") (pin "4-DIN") (pinfunction "DI_4-DIN") (pintype "input"))
      (node (ref "LED6") (pin "2-DOUT") (pinfunction "DO_2-DOUT") (pintype "output"))
    )
    (net (code "48") (name "Net-(OK1-A)") (class "Default")
      (node (ref "OK1") (pin "1") (pinfunction "A_1") (pintype "passive"))
      (node (ref "R106") (pin "2") (pinfunction "2_2") (pintype "passive"))
    )
    (net (code "49") (name "Net-(OK1-A1)") (class "Default")
      (node (ref "OK1") (pin "4") (pinfunction "A1_4") (pintype "passive"))
      (node (ref "R100") (pin "1") (pinfunction "1_1") (pintype "passive"))
      (node (ref "U$9") (pin "3") (pinfunction "G_3") (pintype "passive"))
    )
    (net (code "50") (name "Net-(OK1-A2)") (class "Default")
      (node (ref "OK1") (pin "6") (pinfunction "A2_6") (pintype "passive"))
      (node (ref "R104") (pin "2") (pinfunction "2_2") (pintype "passive"))
    )
    (net (code "51") (name "Net-(OK2-A)") (class "Default")
      (node (ref "OK2") (pin "1") (pinfunction "A_1") (pintype "passive"))
      (node (ref "R107") (pin "2") (pinfunction "2_2") (pintype "passive"))
    )
    (net (code "52") (name "Net-(OK2-A1)") (class "Default")
      (node (ref "OK2") (pin "4") (pinfunction "A1_4") (pintype "passive"))
      (node (ref "R101") (pin "1") (pinfunction "1_1") (pintype "passive"))
      (node (ref "U$8") (pin "3") (pinfunction "G_3") (pintype "passive"))
    )
    (net (code "53") (name "Net-(OK2-A2)") (class "Default")
      (node (ref "OK2") (pin "6") (pinfunction "A2_6") (pintype "passive"))
      (node (ref "R103") (pin "2") (pinfunction "2_2") (pintype "passive"))
    )
    (net (code "54") (name "Net-(OK3-A)") (class "Default")
      (node (ref "OK3") (pin "1") (pinfunction "A_1") (pintype "passive"))
      (node (ref "R108") (pin "2") (pinfunction "2_2") (pintype "passive"))
    )
    (net (code "55") (name "Net-(OK3-A1)") (class "Default")
      (node (ref "OK3") (pin "4") (pinfunction "A1_4") (pintype "passive"))
      (node (ref "R102") (pin "1") (pinfunction "1_1") (pintype "passive"))
      (node (ref "U$10") (pin "3") (pinfunction "G_3") (pintype "passive"))
    )
    (net (code "56") (name "Net-(OK3-A2)") (class "Default")
      (node (ref "OK3") (pin "6") (pinfunction "A2_6") (pintype "passive"))
      (node (ref "R105") (pin "2") (pinfunction "2_2") (pintype "passive"))
    )
    (net (code "57") (name "Net-(OK4-A)") (class "Default")
      (node (ref "D100") (pin "C") (pinfunction "C_C") (pintype "passive"))
      (node (ref "OK4") (pin "1") (pinfunction "A_1") (pintype "passive"))
      (node (ref "R37") (pin "1") (pinfunction "1_1") (pintype "passive"))
    )
    (net (code "58") (name "Net-(OK4-C)") (class "Default")
      (node (ref "D100") (pin "A") (pinfunction "A_A") (pintype "passive"))
      (node (ref "D3") (pin "A") (pinfunction "A_A") (pintype "passive"))
      (node (ref "OK4") (pin "2") (pinfunction "C_2") (pintype "passive"))
    )
    (net (code "59") (name "Net-(OK4-COL)") (class "Default")
      (node (ref "OK4") (pin "5") (pinfunction "COL_5") (pintype "passive"))
      (node (ref "R29") (pin "1") (pinfunction "1_1") (pintype "passive"))
      (node (ref "R35") (pin "2") (pinfunction "2_2") (pintype "passive"))
    )
    (net (code "60") (name "Net-(Q1-D)") (class "Default")
      (node (ref "D2") (pin "A") (pinfunction "A_A") (pintype "passive"))
      (node (ref "K100") (pin "5") (pinfunction "5_5") (pintype "passive"))
      (node (ref "Q1") (pin "3") (pinfunction "D_3") (pintype "passive"))
    )
    (net (code "61") (name "Net-(U$10-A1)") (class "Default")
      (node (ref "R102") (pin "2") (pinfunction "2_2") (pintype "passive"))
      (node (ref "U$10") (pin "1") (pinfunction "A1_1") (pintype "passive"))
      (node (ref "U$101") (pin "P$3") (pinfunction "3_P$3") (pintype "passive"))
    )
    (net (code "62") (name "Net-(U$100-2)") (class "Default")
      (node (ref "K100") (pin "1") (pinfunction "1_1") (pintype "passive"))
      (node (ref "U$100") (pin "P$2") (pinfunction "2_P$2") (pintype "passive"))
    )
    (net (code "63") (name "Net-(U$102-3)") (class "Default")
      (node (ref "R101") (pin "2") (pinfunction "2_2") (pintype "passive"))
      (node (ref "U$102") (pin "P$3") (pinfunction "3_P$3") (pintype "passive"))
      (node (ref "U$8") (pin "1") (pinfunction "A1_1") (pintype "passive"))
    )
    (net (code "64") (name "Net-(U$103-3)") (class "Default")
      (node (ref "R100") (pin "2") (pinfunction "2_2") (pintype "passive"))
      (node (ref "U$103") (pin "P$3") (pinfunction "3_P$3") (pintype "passive"))
      (node (ref "U$9") (pin "1") (pinfunction "A1_1") (pintype "passive"))
    )
    (net (code "65") (name "Net-(U1-RO)") (class "Default")
      (node (ref "R5") (pin "1") (pinfunction "1_1") (pintype "passive"))
      (node (ref "U1") (pin "1") (pinfunction "RO_1") (pintype "bidirectional"))
    )
    (net (code "66") (name "Net-(U2-FB)") (class "Default")
      (node (ref "C12") (pin "1") (pinfunction "1_1") (pintype "passive"))
      (node (ref "R18") (pin "2") (pinfunction "2_2") (pintype "passive"))
      (node (ref "R25") (pin "2") (pinfunction "2_2") (pintype "passive"))
      (node (ref "U2") (pin "3") (pinfunction "FB_3") (pintype "input"))
    )
    (net (code "67") (name "Net-(U2-SW)") (class "Default")
      (node (ref "D1") (pin "A") (pinfunction "A_A") (pintype "passive"))
      (node (ref "L1") (pin "2") (pinfunction "2_2") (pintype "passive"))
      (node (ref "U2") (pin "1") (pinfunction "SW_1") (pintype "passive"))
    )
    (net (code "68") (name "OUT_1_SIG") (class "Default")
      (node (ref "IC1") (pin "25") (pinfunction "25_25") (pintype "bidirectional"))
      (node (ref "R106") (pin "1") (pinfunction "1_1") (pintype "passive"))
      (node (ref "R30") (pin "1") (pinfunction "1_1") (pintype "passive"))
    )
    (net (code "69") (name "OUT_2_SIG") (class "Default")
      (node (ref "IC1") (pin "32") (pinfunction "32_32") (pintype "bidirectional"))
      (node (ref "R107") (pin "1") (pinfunction "1_1") (pintype "passive"))
      (node (ref "R31") (pin "1") (pinfunction "1_1") (pintype "passive"))
    )
    (net (code "70") (name "OUT_3_SIG") (class "Default")
      (node (ref "IC1") (pin "33") (pinfunction "33_33") (pintype "bidirectional"))
      (node (ref "R108") (pin "1") (pinfunction "1_1") (pintype "passive"))
      (node (ref "R32") (pin "1") (pinfunction "1_1") (pintype "passive"))
    )
    (net (code "71") (name "PE") (class "Default")
      (node (ref "P2") (pin "P$1") (pinfunction "P_P$1") (pintype "passive"))
      (node (ref "P2") (pin "P$10") (pinfunction "P_P$10") (pintype "passive"))
      (node (ref "P2") (pin "P$11") (pinfunction "P_P$11") (pintype "passive"))
      (node (ref "P2") (pin "P$2") (pinfunction "P_P$2") (pintype "passive"))
      (node (ref "P2") (pin "P$5") (pinfunction "P_P$5") (pintype "passive"))
      (node (ref "P2") (pin "P$6") (pinfunction "P_P$6") (pintype "passive"))
      (node (ref "P2") (pin "P$7") (pinfunction "P_P$7") (pintype "passive"))
      (node (ref "P2") (pin "P$8") (pinfunction "P_P$8") (pintype "passive"))
      (node (ref "P2") (pin "P$9") (pinfunction "P_P$9") (pintype "passive"))
      (node (ref "U$101") (pin "P$1") (pinfunction "1_P$1") (pintype "passive"))
      (node (ref "U$102") (pin "P$1") (pinfunction "1_P$1") (pintype "passive"))
      (node (ref "U$103") (pin "P$1") (pinfunction "1_P$1") (pintype "passive"))
      (node (ref "U$104") (pin "P$1") (pinfunction "1_P$1") (pintype "passive"))
    )
    (net (code "72") (name "PWM_1") (class "Default")
      (node (ref "K101") (pin "P$2") (pinfunction "2_P$2") (pintype "passive"))
      (node (ref "R109") (pin "2") (pinfunction "2_2") (pintype "passive"))
      (node (ref "R28") (pin "1") (pinfunction "1_1") (pintype "passive"))
    )
    (net (code "73") (name "PWM_2") (class "Default")
      (node (ref "K101") (pin "P$3") (pinfunction "3_P$3") (pintype "passive"))
      (node (ref "R110") (pin "2") (pinfunction "2_2") (pintype "passive"))
      (node (ref "R27") (pin "1") (pinfunction "1_1") (pintype "passive"))
    )
    (net (code "74") (name "PWM_3") (class "Default")
      (node (ref "K101") (pin "P$4") (pinfunction "4_P$4") (pintype "passive"))
      (node (ref "R111") (pin "2") (pinfunction "2_2") (pintype "passive"))
      (node (ref "R26") (pin "1") (pinfunction "1_1") (pintype "passive"))
    )
    (net (code "75") (name "RELAY_SIG") (class "Default")
      (node (ref "IC1") (pin "27") (pinfunction "27_27") (pintype "bidirectional"))
      (node (ref "Q1") (pin "1") (pinfunction "G_1") (pintype "passive"))
      (node (ref "R33") (pin "1") (pinfunction "1_1") (pintype "passive"))
      (node (ref "R34") (pin "1") (pinfunction "1_1") (pintype "passive"))
    )
    (net (code "76") (name "R_NC") (class "Default")
      (node (ref "K100") (pin "4") (pinfunction "4_4") (pintype "passive"))
      (node (ref "U$100") (pin "P$1") (pinfunction "1_P$1") (pintype "passive"))
    )
    (net (code "77") (name "R_NO") (class "Default")
      (node (ref "K100") (pin "3") (pinfunction "3_3") (pintype "passive"))
      (node (ref "U$100") (pin "P$3") (pinfunction "3_P$3") (pintype "passive"))
    )
    (net (code "78") (name "SCL") (class "Default")
      (node (ref "C2") (pin "1") (pinfunction "1_1") (pintype "passive"))
      (node (ref "IC1") (pin "22") (pinfunction "22_22") (pintype "bidirectional"))
      (node (ref "JP1") (pin "4") (pinfunction "4_4") (pintype "passive"))
      (node (ref "R4") (pin "1") (pinfunction "1_1") (pintype "passive"))
    )
    (net (code "79") (name "SDA") (class "Default")
      (node (ref "C9") (pin "1") (pinfunction "1_1") (pintype "passive"))
      (node (ref "IC1") (pin "21") (pinfunction "21_21") (pintype "bidirectional"))
      (node (ref "JP1") (pin "3") (pinfunction "3_3") (pintype "passive"))
      (node (ref "R6") (pin "1") (pinfunction "1_1") (pintype "passive"))
    )
    (net (code "80") (name "SENS_IN") (class "Default")
      (node (ref "R36") (pin "2") (pinfunction "2_2") (pintype "passive"))
      (node (ref "U$104") (pin "P$4") (pinfunction "4_P$4") (pintype "passive"))
    )
    (net (code "81") (name "ZC_SIG") (class "Default")
      (node (ref "C21") (pin "1") (pinfunction "1_1") (pintype "passive"))
      (node (ref "IC1") (pin "39") (pinfunction "39_39") (pintype "bidirectional"))
      (node (ref "R35") (pin "1") (pinfunction "1_1") (pintype "passive"))
    )
    (net (code "82") (name "unconnected-(JP1-Pad1)") (class "Default")
      (node (ref "JP1") (pin "1") (pinfunction "1_1") (pintype "passive"))
    )
    (net (code "83") (name "unconnected-(JP1-Pad2)") (class "Default")
      (node (ref "JP1") (pin "2") (pinfunction "2_2") (pintype "passive"))
    )
    (net (code "84") (name "unconnected-(LED14-DO-Pad2-DOUT)") (class "Default")
      (node (ref "LED14") (pin "2-DOUT") (pinfunction "DO_2-DOUT") (pintype "output"))
    )
    (net (code "85") (name "unconnected-(OK4-BAS-Pad6)") (class "Default")
      (node (ref "OK4") (pin "6") (pinfunction "BAS_6") (pintype "passive"))
    )
  )
)
